# KickerBoard-new-switchreg-rerouted.net
KiCad netlist of a schematic drawn in EAGLE
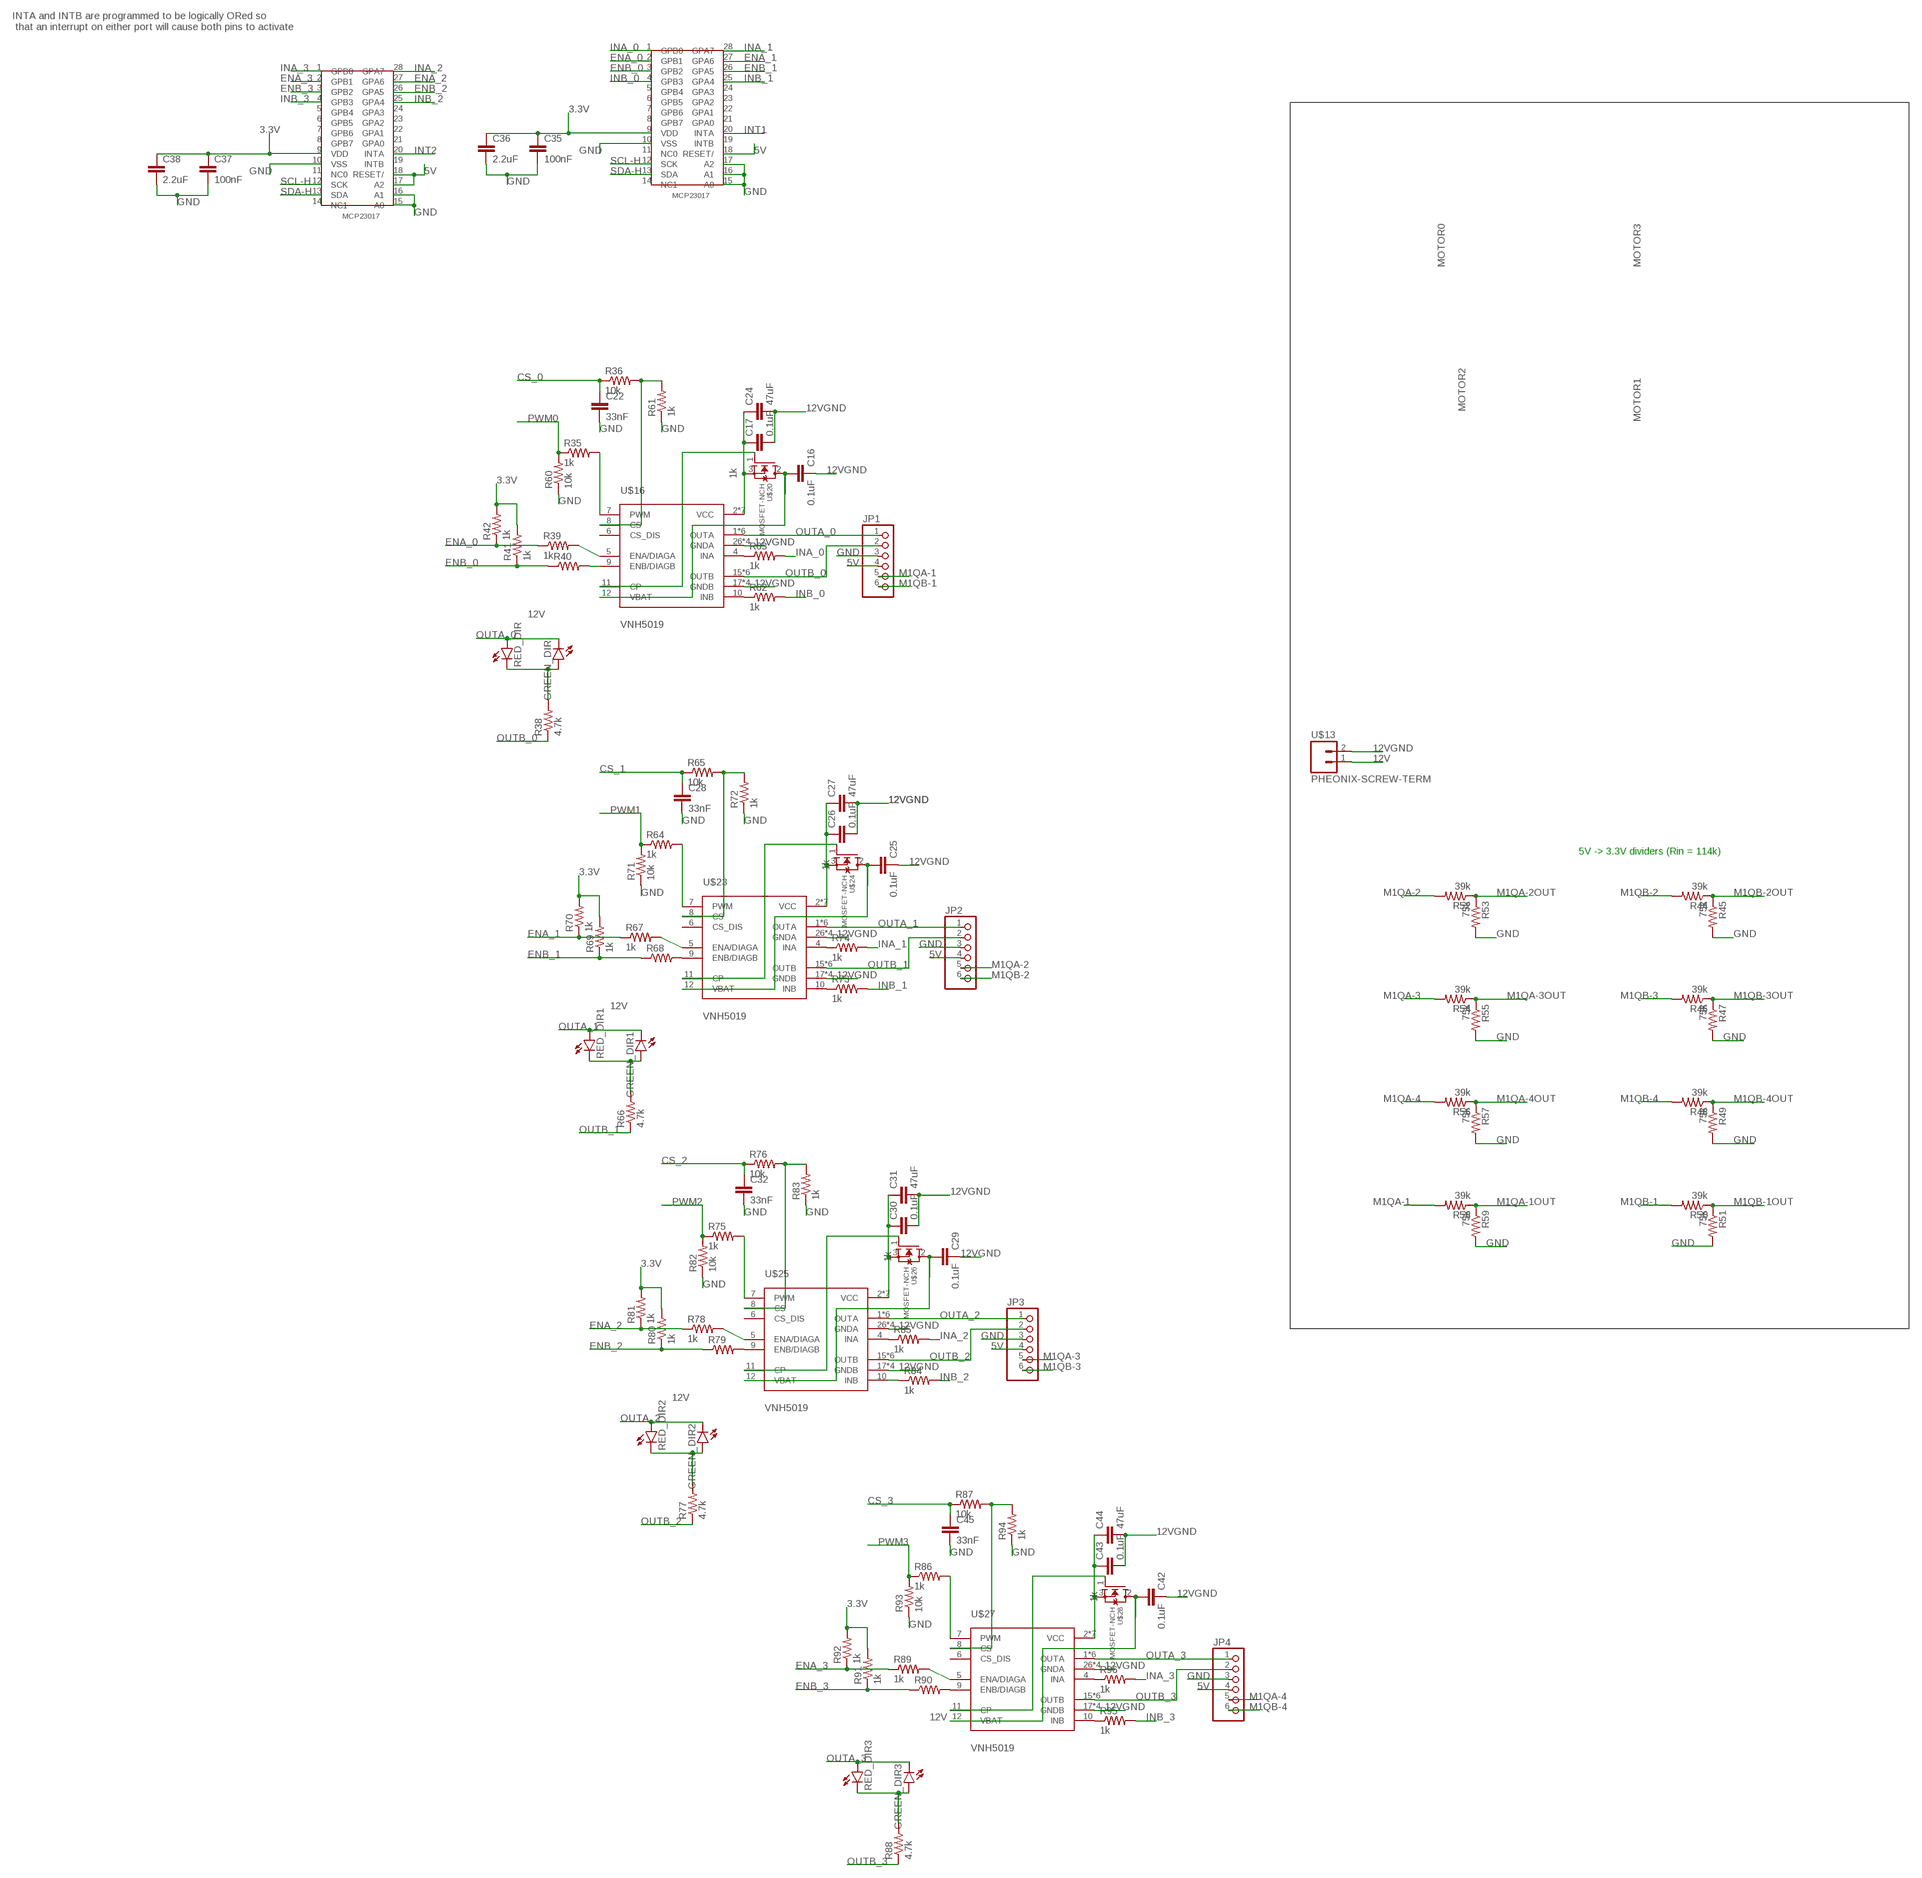
[diagram p0: schematic, sheet 1, part 1 of 3]
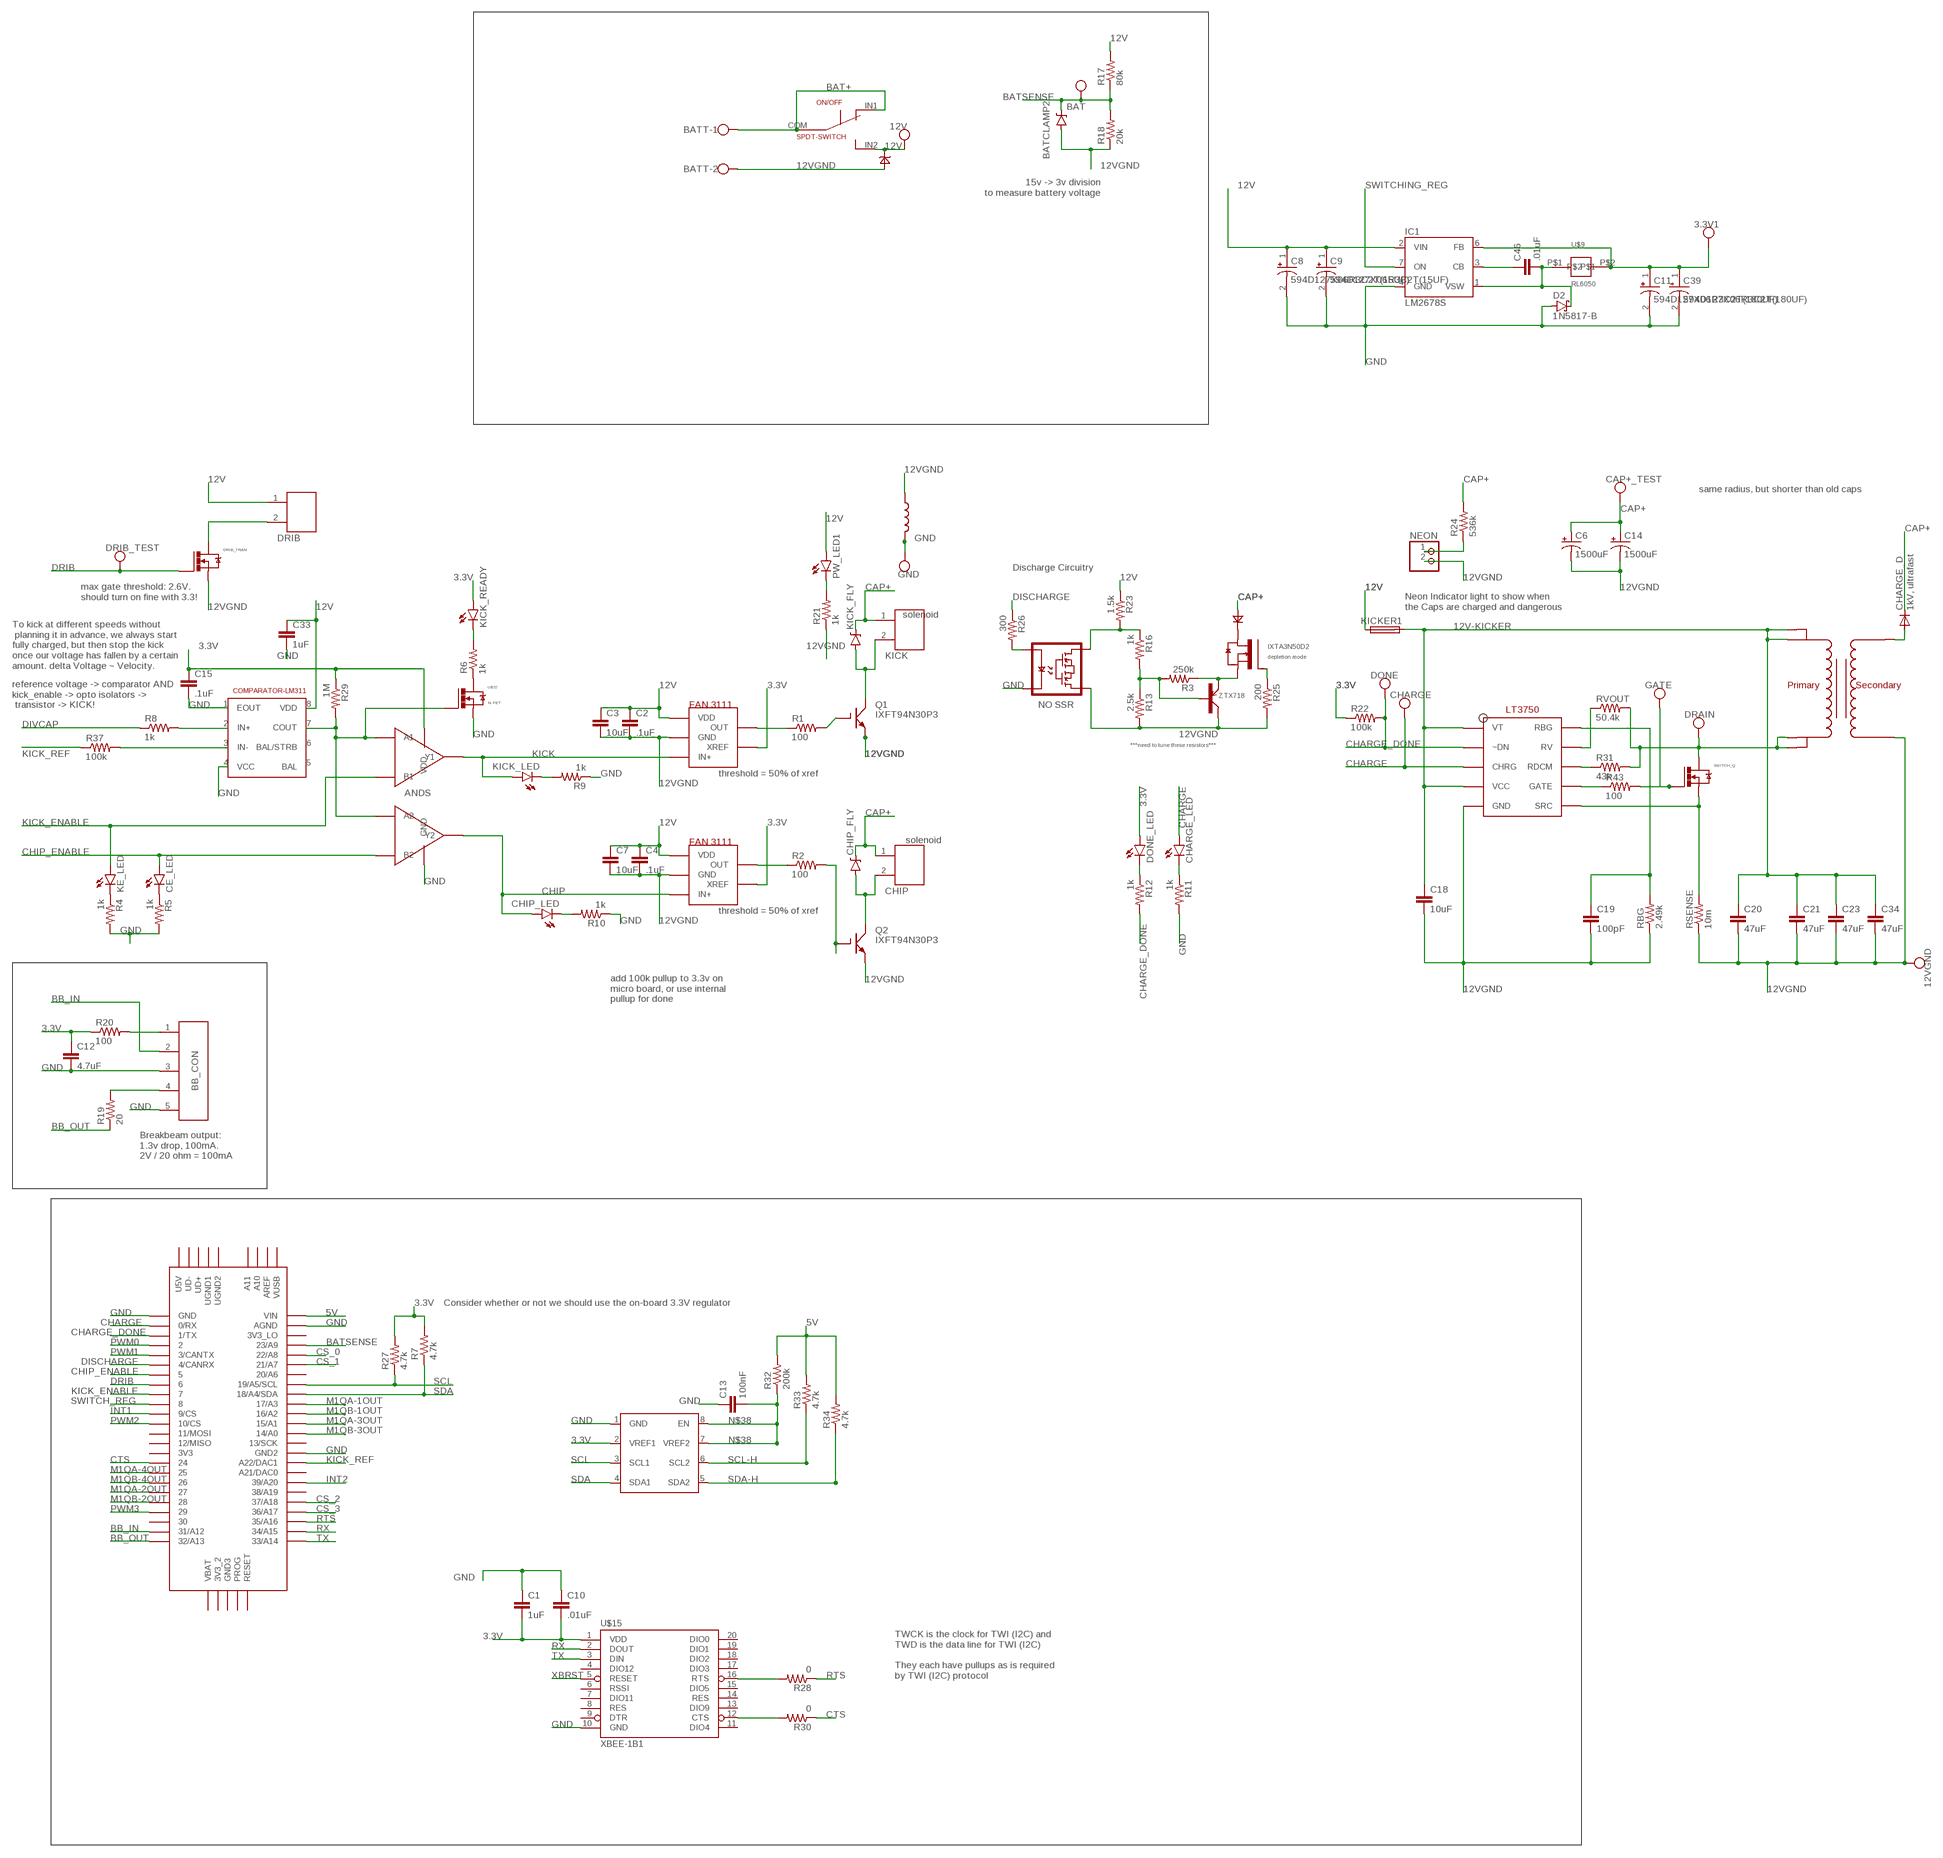
[diagram p1: schematic, sheet 1, part 2 of 3]
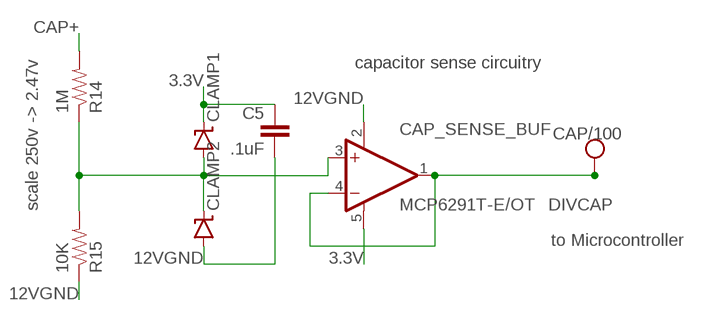
[diagram p2: schematic, sheet 1, part 3 of 3]

(export (version "E")
  (design (tool "Eeschema 10.0.6"))
  (components
    (comp (ref "3.3V1")
      (value "TEST_PT")
      (footprint "eagle-import:TESTING_PT")
      (libsource (lib "eagle-import") (part "TEST_PT"))
    )
    (comp (ref "12V")
      (value "TEST_PT")
      (footprint "eagle-import:TESTING_PT")
      (libsource (lib "eagle-import") (part "TEST_PT"))
    )
    (comp (ref "12VGND")
      (value "TEST_PT")
      (footprint "eagle-import:TESTING_PT")
      (libsource (lib "eagle-import") (part "TEST_PT"))
    )
    (comp (ref "ANDS")
      (value "AND-DUAL")
      (footprint "eagle-import:TSSOP8")
      (libsource (lib "eagle-import") (part "AND-DUAL"))
    )
    (comp (ref "BAT")
      (value "TEST_PT")
      (footprint "eagle-import:TESTING_PT")
      (libsource (lib "eagle-import") (part "TEST_PT"))
    )
    (comp (ref "BATCLAMP2")
      (value "DIODE-ZENERDO214AC")
      (footprint "eagle-import:DO214AC")
      (libsource (lib "eagle-import") (part "DIODE-ZENERDO214AC"))
    )
    (comp (ref "BATT")
      (value "W237-102")
      (footprint "eagle-import:W237-102")
      (fields (field (name "MPN") "237-102"))
      (libsource (lib "eagle-import") (part "W237-102"))
    )
    (comp (ref "BB_CON")
      (value "JST-5")
      (footprint "eagle-import:JST-5-2MM")
      (libsource (lib "eagle-import") (part "JST-5"))
    )
    (comp (ref "C1")
      (value "1uF")
      (footprint "eagle-import:1206")
      (libsource (lib "eagle-import") (part "CAP1206"))
    )
    (comp (ref "C2")
      (value ".1uF")
      (footprint "eagle-import:1206")
      (libsource (lib "eagle-import") (part "CAP1206"))
    )
    (comp (ref "C3")
      (value "10uF")
      (footprint "eagle-import:1206")
      (libsource (lib "eagle-import") (part "CAP1206"))
    )
    (comp (ref "C4")
      (value ".1uF")
      (footprint "eagle-import:1206")
      (libsource (lib "eagle-import") (part "CAP1206"))
    )
    (comp (ref "C5")
      (value ".1uF")
      (footprint "eagle-import:0805")
      (libsource (lib "eagle-import") (part "CAP0805"))
    )
    (comp (ref "C6")
      (value "1500uF")
      (footprint "eagle-import:EB35D")
      (libsource (lib "eagle-import") (part "CPOL-USE10-35"))
    )
    (comp (ref "C7")
      (value "10uF")
      (footprint "eagle-import:1206")
      (libsource (lib "eagle-import") (part "CAP1206"))
    )
    (comp (ref "C8")
      (value "594D127X06R3C2T(15UF)")
      (footprint "eagle-import:CAPCP7132X250N")
      (fields (field (name "MF") "Vishay") (field (name "MP") "594D127X06R3C2T"))
      (libsource (lib "eagle-import") (part "594D127X06R3C2T(15UF)"))
    )
    (comp (ref "C9")
      (value "594D127X06R3C2T(15UF)")
      (footprint "eagle-import:CAPCP7132X250N")
      (fields (field (name "MF") "Vishay") (field (name "MP") "594D127X06R3C2T"))
      (libsource (lib "eagle-import") (part "594D127X06R3C2T(15UF)"))
    )
    (comp (ref "C10")
      (value ".01uF")
      (footprint "eagle-import:1206")
      (libsource (lib "eagle-import") (part "CAP1206"))
    )
    (comp (ref "C11")
      (value "594D127X06R3C2T(180UF)")
      (footprint "eagle-import:CAPCP7132X250N")
      (fields (field (name "MF") "Vishay") (field (name "MP") "594D127X06R3C2T"))
      (libsource (lib "eagle-import") (part "594D127X06R3C2T(180UF)"))
    )
    (comp (ref "C12")
      (value "4.7uF")
      (footprint "eagle-import:0805")
      (libsource (lib "eagle-import") (part "CAP0805"))
    )
    (comp (ref "C13")
      (value "100nF")
      (footprint "eagle-import:0805")
      (libsource (lib "eagle-import") (part "CAP0805"))
    )
    (comp (ref "C14")
      (value "1500uF")
      (footprint "eagle-import:EB35D")
      (libsource (lib "eagle-import") (part "CPOL-USE10-35"))
    )
    (comp (ref "C15")
      (value ".1uF")
      (footprint "eagle-import:0805")
      (libsource (lib "eagle-import") (part "CAP0805"))
    )
    (comp (ref "C16")
      (value "0.1uF")
      (footprint "eagle-import:0805")
      (libsource (lib "eagle-import") (part "CAP0805"))
    )
    (comp (ref "C17")
      (value "0.1uF")
      (footprint "eagle-import:0805")
      (libsource (lib "eagle-import") (part "CAP0805"))
    )
    (comp (ref "C18")
      (value "10uF")
      (footprint "eagle-import:0805")
      (libsource (lib "eagle-import") (part "CAP0805"))
    )
    (comp (ref "C19")
      (value "100pF")
      (footprint "eagle-import:0805")
      (libsource (lib "eagle-import") (part "CAP0805"))
    )
    (comp (ref "C20")
      (value "47uF")
      (footprint "eagle-import:1206")
      (libsource (lib "eagle-import") (part "CAP1206"))
    )
    (comp (ref "C21")
      (value "47uF")
      (footprint "eagle-import:1206")
      (libsource (lib "eagle-import") (part "CAP1206"))
    )
    (comp (ref "C22")
      (value "33nF")
      (footprint "eagle-import:0805")
      (libsource (lib "eagle-import") (part "CAP0805"))
    )
    (comp (ref "C23")
      (value "47uF")
      (footprint "eagle-import:1206")
      (libsource (lib "eagle-import") (part "CAP1206"))
    )
    (comp (ref "C24")
      (value "47uF")
      (footprint "eagle-import:1206")
      (libsource (lib "eagle-import") (part "CAP1206"))
    )
    (comp (ref "C25")
      (value "0.1uF")
      (footprint "eagle-import:0805")
      (libsource (lib "eagle-import") (part "CAP0805"))
    )
    (comp (ref "C26")
      (value "0.1uF")
      (footprint "eagle-import:0805")
      (libsource (lib "eagle-import") (part "CAP0805"))
    )
    (comp (ref "C27")
      (value "47uF")
      (footprint "eagle-import:1206")
      (libsource (lib "eagle-import") (part "CAP1206"))
    )
    (comp (ref "C28")
      (value "33nF")
      (footprint "eagle-import:0805")
      (libsource (lib "eagle-import") (part "CAP0805"))
    )
    (comp (ref "C29")
      (value "0.1uF")
      (footprint "eagle-import:0805")
      (libsource (lib "eagle-import") (part "CAP0805"))
    )
    (comp (ref "C30")
      (value "0.1uF")
      (footprint "eagle-import:0805")
      (libsource (lib "eagle-import") (part "CAP0805"))
    )
    (comp (ref "C31")
      (value "47uF")
      (footprint "eagle-import:1206")
      (libsource (lib "eagle-import") (part "CAP1206"))
    )
    (comp (ref "C32")
      (value "33nF")
      (footprint "eagle-import:0805")
      (libsource (lib "eagle-import") (part "CAP0805"))
    )
    (comp (ref "C33")
      (value "1uF")
      (footprint "eagle-import:1206")
      (libsource (lib "eagle-import") (part "CAP1206"))
    )
    (comp (ref "C34")
      (value "47uF")
      (footprint "eagle-import:1206")
      (libsource (lib "eagle-import") (part "CAP1206"))
    )
    (comp (ref "C35")
      (value "100nF")
      (footprint "eagle-import:0805")
      (libsource (lib "eagle-import") (part "CAP0805"))
    )
    (comp (ref "C36")
      (value "2.2uF")
      (footprint "eagle-import:0805")
      (libsource (lib "eagle-import") (part "CAP0805"))
    )
    (comp (ref "C37")
      (value "100nF")
      (footprint "eagle-import:0805")
      (libsource (lib "eagle-import") (part "CAP0805"))
    )
    (comp (ref "C38")
      (value "2.2uF")
      (footprint "eagle-import:0805")
      (libsource (lib "eagle-import") (part "CAP0805"))
    )
    (comp (ref "C39")
      (value "594D127X06R3C2T(180UF)")
      (footprint "eagle-import:CAPCP7132X250N")
      (fields (field (name "MF") "Vishay") (field (name "MP") "594D127X06R3C2T"))
      (libsource (lib "eagle-import") (part "594D127X06R3C2T(180UF)"))
    )
    (comp (ref "C42")
      (value "0.1uF")
      (footprint "eagle-import:0805")
      (libsource (lib "eagle-import") (part "CAP0805"))
    )
    (comp (ref "C43")
      (value "0.1uF")
      (footprint "eagle-import:0805")
      (libsource (lib "eagle-import") (part "CAP0805"))
    )
    (comp (ref "C44")
      (value "47uF")
      (footprint "eagle-import:1206")
      (libsource (lib "eagle-import") (part "CAP1206"))
    )
    (comp (ref "C45")
      (value "33nF")
      (footprint "eagle-import:0805")
      (libsource (lib "eagle-import") (part "CAP0805"))
    )
    (comp (ref "C46")
      (value ".01uF")
      (footprint "eagle-import:0805")
      (libsource (lib "eagle-import") (part "CAP0805"))
    )
    (comp (ref "CAP+_TEST")
      (value "TEST_PT")
      (footprint "eagle-import:TESTING_PT")
      (libsource (lib "eagle-import") (part "TEST_PT"))
    )
    (comp (ref "CAP/100")
      (value "TEST_PT")
      (footprint "eagle-import:TESTING_PT")
      (libsource (lib "eagle-import") (part "TEST_PT"))
    )
    (comp (ref "CAP_SENSE_BUF")
      (value "MCP6291T-E/OT")
      (footprint "eagle-import:SOT23-5")
      (libsource (lib "eagle-import") (part "MCP6291T-E/OT"))
    )
    (comp (ref "CE_LED")
      (value "LED1206")
      (footprint "eagle-import:LED-1206")
      (libsource (lib "eagle-import") (part "LED1206"))
    )
    (comp (ref "CHARGE")
      (value "TEST_PT")
      (footprint "eagle-import:TESTING_PT")
      (libsource (lib "eagle-import") (part "TEST_PT"))
    )
    (comp (ref "CHARGE_D")
      (value "1kV, ultrafast")
      (footprint "eagle-import:DO214AC")
      (libsource (lib "eagle-import") (part "DIODE-DO214AC"))
    )
    (comp (ref "CHARGE_LED")
      (value "LED1206")
      (footprint "eagle-import:LED-1206")
      (libsource (lib "eagle-import") (part "LED1206"))
    )
    (comp (ref "CHARGE_U")
      (value "LT3750")
      (footprint "eagle-import:10-MSOP")
      (libsource (lib "eagle-import") (part "LT3750"))
    )
    (comp (ref "CHIP")
      (value "JST-22MM")
      (footprint "eagle-import:JST-2-2MM")
      (libsource (lib "eagle-import") (part "JST-22MM"))
    )
    (comp (ref "CHIP_FLY")
      (value "DIODE-ZENERDO214AB")
      (footprint "eagle-import:DO214AB")
      (libsource (lib "eagle-import") (part "DIODE-ZENERDO214AB"))
    )
    (comp (ref "CHIP_LED")
      (value "LED1206")
      (footprint "eagle-import:LED-1206")
      (libsource (lib "eagle-import") (part "LED1206"))
    )
    (comp (ref "CLAMP1")
      (value "DIODE-ZENERDO214AC")
      (footprint "eagle-import:DO214AC")
      (libsource (lib "eagle-import") (part "DIODE-ZENERDO214AC"))
    )
    (comp (ref "CLAMP2")
      (value "DIODE-ZENERDO214AC")
      (footprint "eagle-import:DO214AC")
      (libsource (lib "eagle-import") (part "DIODE-ZENERDO214AC"))
    )
    (comp (ref "D2")
      (value "1N5817-B")
      (footprint "eagle-import:DO41-7.6")
      (libsource (lib "eagle-import") (part "1N5817-B"))
    )
    (comp (ref "DONE")
      (value "TEST_PT")
      (footprint "eagle-import:TESTING_PT")
      (libsource (lib "eagle-import") (part "TEST_PT"))
    )
    (comp (ref "DONE_LED")
      (value "LED1206")
      (footprint "eagle-import:LED-1206")
      (libsource (lib "eagle-import") (part "LED1206"))
    )
    (comp (ref "DRAIN")
      (value "TEST_PT")
      (footprint "eagle-import:TESTING_PT")
      (libsource (lib "eagle-import") (part "TEST_PT"))
    )
    (comp (ref "DRIB")
      (value "JST-22MM")
      (footprint "eagle-import:JST-2-2MM")
      (libsource (lib "eagle-import") (part "JST-22MM"))
    )
    (comp (ref "DRIB_TEST")
      (value "TEST_PT")
      (footprint "eagle-import:TESTING_PT")
      (libsource (lib "eagle-import") (part "TEST_PT"))
    )
    (comp (ref "DRIB_TRAN")
      (value "N-MOSFETDPAK")
      (footprint "eagle-import:DPAK")
      (libsource (lib "eagle-import") (part "N-MOSFETDPAK"))
    )
    (comp (ref "GATE")
      (value "TEST_PT")
      (footprint "eagle-import:TESTING_PT")
      (libsource (lib "eagle-import") (part "TEST_PT"))
    )
    (comp (ref "GND")
      (value "TEST_PT")
      (footprint "eagle-import:TESTING_PT")
      (libsource (lib "eagle-import") (part "TEST_PT"))
    )
    (comp (ref "GREEN_DIR")
      (value "LED1206")
      (footprint "eagle-import:LED-1206")
      (libsource (lib "eagle-import") (part "LED1206"))
    )
    (comp (ref "GREEN_DIR1")
      (value "LED1206")
      (footprint "eagle-import:LED-1206")
      (libsource (lib "eagle-import") (part "LED1206"))
    )
    (comp (ref "GREEN_DIR2")
      (value "LED1206")
      (footprint "eagle-import:LED-1206")
      (libsource (lib "eagle-import") (part "LED1206"))
    )
    (comp (ref "GREEN_DIR3")
      (value "LED1206")
      (footprint "eagle-import:LED-1206")
      (libsource (lib "eagle-import") (part "LED1206"))
    )
    (comp (ref "IC1")
      (value "LM2678S")
      (footprint "eagle-import:TO263-7")
      (libsource (lib "eagle-import") (part "LM2678S"))
    )
    (comp (ref "JP1")
      (value "PINHD-1X6")
      (footprint "eagle-import:1X06")
      (libsource (lib "eagle-import") (part "PINHD-1X6"))
    )
    (comp (ref "JP2")
      (value "PINHD-1X6")
      (footprint "eagle-import:1X06")
      (libsource (lib "eagle-import") (part "PINHD-1X6"))
    )
    (comp (ref "JP3")
      (value "PINHD-1X6")
      (footprint "eagle-import:1X06")
      (libsource (lib "eagle-import") (part "PINHD-1X6"))
    )
    (comp (ref "JP4")
      (value "PINHD-1X6")
      (footprint "eagle-import:1X06")
      (libsource (lib "eagle-import") (part "PINHD-1X6"))
    )
    (comp (ref "KE_LED")
      (value "LED1206")
      (footprint "eagle-import:LED-1206")
      (libsource (lib "eagle-import") (part "LED1206"))
    )
    (comp (ref "KICK")
      (value "JST-22MM")
      (footprint "eagle-import:JST-2-2MM")
      (libsource (lib "eagle-import") (part "JST-22MM"))
    )
    (comp (ref "KICKER1")
      (value "TR5")
      (footprint "eagle-import:TR5")
      (libsource (lib "eagle-import") (part "TR5"))
    )
    (comp (ref "KICK_FLY")
      (value "DIODE-ZENERDO214AB")
      (footprint "eagle-import:DO214AB")
      (libsource (lib "eagle-import") (part "DIODE-ZENERDO214AB"))
    )
    (comp (ref "KICK_LED")
      (value "LED1206")
      (footprint "eagle-import:LED-1206")
      (libsource (lib "eagle-import") (part "LED1206"))
    )
    (comp (ref "KICK_READY")
      (value "LED1206")
      (footprint "eagle-import:LED-1206")
      (libsource (lib "eagle-import") (part "LED1206"))
    )
    (comp (ref "NEON")
      (value "PINHD-1X2")
      (footprint "eagle-import:1X02")
      (libsource (lib "eagle-import") (part "PINHD-1X2"))
    )
    (comp (ref "ON/OFF")
      (value "SPDT-SWITCH")
      (footprint "eagle-import:CK_SWITCH")
      (libsource (lib "eagle-import") (part "SPDT-SWITCH"))
    )
    (comp (ref "PW_LED1")
      (value "LED1206")
      (footprint "eagle-import:LED-1206")
      (libsource (lib "eagle-import") (part "LED1206"))
    )
    (comp (ref "Q1")
      (value "IXFT94N30P3")
      (footprint "eagle-import:TO268")
      (libsource (lib "eagle-import") (part "IXG?N170T6"))
    )
    (comp (ref "Q2")
      (value "IXFT94N30P3")
      (footprint "eagle-import:TO268")
      (libsource (lib "eagle-import") (part "IXG?N170T6"))
    )
    (comp (ref "R1")
      (value "100")
      (footprint "eagle-import:0805")
      (libsource (lib "eagle-import") (part "SparkFun-Resistors_RESISTOR0805-RES"))
    )
    (comp (ref "R2")
      (value "100")
      (footprint "eagle-import:0805")
      (libsource (lib "eagle-import") (part "SparkFun-Resistors_RESISTOR0805-RES"))
    )
    (comp (ref "R3")
      (value "250k")
      (footprint "eagle-import:0805")
      (libsource (lib "eagle-import") (part "RESISTOR0805-RES"))
    )
    (comp (ref "R4")
      (value "1k")
      (footprint "eagle-import:0805")
      (libsource (lib "eagle-import") (part "RESISTOR0805-RES"))
    )
    (comp (ref "R5")
      (value "1k")
      (footprint "eagle-import:0805")
      (libsource (lib "eagle-import") (part "RESISTOR0805-RES"))
    )
    (comp (ref "R6")
      (value "1k")
      (footprint "eagle-import:0805")
      (libsource (lib "eagle-import") (part "RESISTOR0805-RES"))
    )
    (comp (ref "R7")
      (value "4.7k")
      (footprint "eagle-import:0805")
      (libsource (lib "eagle-import") (part "SparkFun-Resistors_RESISTOR0805-RES"))
    )
    (comp (ref "R8")
      (value "1k")
      (footprint "eagle-import:0805")
      (libsource (lib "eagle-import") (part "RESISTOR0805-RES"))
    )
    (comp (ref "R9")
      (value "1k")
      (footprint "eagle-import:0805")
      (libsource (lib "eagle-import") (part "RESISTOR0805-RES"))
    )
    (comp (ref "R10")
      (value "1k")
      (footprint "eagle-import:0805")
      (libsource (lib "eagle-import") (part "RESISTOR0805-RES"))
    )
    (comp (ref "R11")
      (value "1k")
      (footprint "eagle-import:0805")
      (libsource (lib "eagle-import") (part "RESISTOR0805-RES"))
    )
    (comp (ref "R12")
      (value "1k")
      (footprint "eagle-import:0805")
      (libsource (lib "eagle-import") (part "RESISTOR0805-RES"))
    )
    (comp (ref "R13")
      (value "2.5k")
      (footprint "eagle-import:0805")
      (libsource (lib "eagle-import") (part "RESISTOR0805-RES"))
    )
    (comp (ref "R14")
      (value "1M")
      (footprint "eagle-import:0805")
      (libsource (lib "eagle-import") (part "SparkFun-Resistors_RESISTOR0805-RES"))
    )
    (comp (ref "R15")
      (value "10K")
      (footprint "eagle-import:0805")
      (libsource (lib "eagle-import") (part "SparkFun-Resistors_RESISTOR0805-RES"))
    )
    (comp (ref "R16")
      (value "1k")
      (footprint "eagle-import:0805")
      (libsource (lib "eagle-import") (part "RESISTOR0805-RES"))
    )
    (comp (ref "R17")
      (value "80k")
      (footprint "eagle-import:0805")
      (libsource (lib "eagle-import") (part "RESISTOR0805-RES"))
    )
    (comp (ref "R18")
      (value "20k")
      (footprint "eagle-import:0805")
      (libsource (lib "eagle-import") (part "RESISTOR0805-RES"))
    )
    (comp (ref "R19")
      (value "20")
      (footprint "eagle-import:0805")
      (libsource (lib "eagle-import") (part "RESISTOR0805-RES"))
    )
    (comp (ref "R20")
      (value "100")
      (footprint "eagle-import:0805")
      (libsource (lib "eagle-import") (part "RESISTOR0805-RES"))
    )
    (comp (ref "R21")
      (value "1k")
      (footprint "eagle-import:0805")
      (libsource (lib "eagle-import") (part "RESISTOR0805-RES"))
    )
    (comp (ref "R22")
      (value "100k")
      (footprint "eagle-import:0805")
      (libsource (lib "eagle-import") (part "RESISTOR0805-RES"))
    )
    (comp (ref "R23")
      (value "1.5k")
      (footprint "eagle-import:0805")
      (libsource (lib "eagle-import") (part "RESISTOR0805-RES"))
    )
    (comp (ref "R24")
      (value "536k")
      (footprint "eagle-import:0805")
      (libsource (lib "eagle-import") (part "RESISTOR0805-RES"))
    )
    (comp (ref "R25")
      (value "200")
      (footprint "eagle-import:0805")
      (libsource (lib "eagle-import") (part "RESISTOR0805-RES"))
    )
    (comp (ref "R26")
      (value "300")
      (footprint "eagle-import:0805")
      (libsource (lib "eagle-import") (part "RESISTOR0805-RES"))
    )
    (comp (ref "R27")
      (value "4.7k")
      (footprint "eagle-import:0805")
      (libsource (lib "eagle-import") (part "SparkFun-Resistors_RESISTOR0805-RES"))
    )
    (comp (ref "R28")
      (value "0")
      (footprint "eagle-import:0805")
      (libsource (lib "eagle-import") (part "SparkFun-Resistors_RESISTOR0805-RES"))
    )
    (comp (ref "R29")
      (value "1M")
      (footprint "eagle-import:0805")
      (libsource (lib "eagle-import") (part "RESISTOR0805-RES"))
    )
    (comp (ref "R30")
      (value "0")
      (footprint "eagle-import:0805")
      (libsource (lib "eagle-import") (part "SparkFun-Resistors_RESISTOR0805-RES"))
    )
    (comp (ref "R31")
      (value "43k")
      (footprint "eagle-import:0805")
      (libsource (lib "eagle-import") (part "RESISTOR0805-RES"))
    )
    (comp (ref "R32")
      (value "200k")
      (footprint "eagle-import:0805")
      (libsource (lib "eagle-import") (part "SparkFun-Resistors_RESISTOR0805-RES"))
    )
    (comp (ref "R33")
      (value "4.7k")
      (footprint "eagle-import:0805")
      (libsource (lib "eagle-import") (part "SparkFun-Resistors_RESISTOR0805-RES"))
    )
    (comp (ref "R34")
      (value "4.7k")
      (footprint "eagle-import:0805")
      (libsource (lib "eagle-import") (part "SparkFun-Resistors_RESISTOR0805-RES"))
    )
    (comp (ref "R35")
      (value "1k")
      (footprint "eagle-import:0805")
      (libsource (lib "eagle-import") (part "RESISTOR0805-RES"))
    )
    (comp (ref "R36")
      (value "10k")
      (footprint "eagle-import:0805")
      (libsource (lib "eagle-import") (part "RESISTOR0805-RES"))
    )
    (comp (ref "R37")
      (value "100k")
      (footprint "eagle-import:0805")
      (libsource (lib "eagle-import") (part "RESISTOR0805-RES"))
    )
    (comp (ref "R38")
      (value "4.7k")
      (footprint "eagle-import:0805")
      (libsource (lib "eagle-import") (part "RESISTOR0805-RES"))
    )
    (comp (ref "R39")
      (value "1k")
      (footprint "eagle-import:0805")
      (libsource (lib "eagle-import") (part "RESISTOR0805-RES"))
    )
    (comp (ref "R40")
      (value "1k")
      (footprint "eagle-import:0805")
      (libsource (lib "eagle-import") (part "RESISTOR0805-RES"))
    )
    (comp (ref "R41")
      (value "1k")
      (footprint "eagle-import:0805")
      (libsource (lib "eagle-import") (part "RESISTOR0805-RES"))
    )
    (comp (ref "R42")
      (value "1k")
      (footprint "eagle-import:0805")
      (libsource (lib "eagle-import") (part "RESISTOR0805-RES"))
    )
    (comp (ref "R43")
      (value "100")
      (footprint "eagle-import:0805")
      (libsource (lib "eagle-import") (part "RESISTOR0805-RES"))
    )
    (comp (ref "R44")
      (value "39k")
      (footprint "eagle-import:0805")
      (libsource (lib "eagle-import") (part "RESISTOR0805-RES"))
    )
    (comp (ref "R45")
      (value "75k")
      (footprint "eagle-import:0805")
      (libsource (lib "eagle-import") (part "RESISTOR0805-RES"))
    )
    (comp (ref "R46")
      (value "39k")
      (footprint "eagle-import:0805")
      (libsource (lib "eagle-import") (part "RESISTOR0805-RES"))
    )
    (comp (ref "R47")
      (value "75k")
      (footprint "eagle-import:0805")
      (libsource (lib "eagle-import") (part "RESISTOR0805-RES"))
    )
    (comp (ref "R48")
      (value "39k")
      (footprint "eagle-import:0805")
      (libsource (lib "eagle-import") (part "RESISTOR0805-RES"))
    )
    (comp (ref "R49")
      (value "75k")
      (footprint "eagle-import:0805")
      (libsource (lib "eagle-import") (part "RESISTOR0805-RES"))
    )
    (comp (ref "R50")
      (value "39k")
      (footprint "eagle-import:0805")
      (libsource (lib "eagle-import") (part "RESISTOR0805-RES"))
    )
    (comp (ref "R51")
      (value "75k")
      (footprint "eagle-import:0805")
      (libsource (lib "eagle-import") (part "RESISTOR0805-RES"))
    )
    (comp (ref "R52")
      (value "39k")
      (footprint "eagle-import:0805")
      (libsource (lib "eagle-import") (part "RESISTOR0805-RES"))
    )
    (comp (ref "R53")
      (value "75k")
      (footprint "eagle-import:0805")
      (libsource (lib "eagle-import") (part "RESISTOR0805-RES"))
    )
    (comp (ref "R54")
      (value "39k")
      (footprint "eagle-import:0805")
      (libsource (lib "eagle-import") (part "RESISTOR0805-RES"))
    )
    (comp (ref "R55")
      (value "75k")
      (footprint "eagle-import:0805")
      (libsource (lib "eagle-import") (part "RESISTOR0805-RES"))
    )
    (comp (ref "R56")
      (value "39k")
      (footprint "eagle-import:0805")
      (libsource (lib "eagle-import") (part "RESISTOR0805-RES"))
    )
    (comp (ref "R57")
      (value "75k")
      (footprint "eagle-import:0805")
      (libsource (lib "eagle-import") (part "RESISTOR0805-RES"))
    )
    (comp (ref "R58")
      (value "39k")
      (footprint "eagle-import:0805")
      (libsource (lib "eagle-import") (part "RESISTOR0805-RES"))
    )
    (comp (ref "R59")
      (value "75k")
      (footprint "eagle-import:0805")
      (libsource (lib "eagle-import") (part "RESISTOR0805-RES"))
    )
    (comp (ref "R60")
      (value "10k")
      (footprint "eagle-import:0805")
      (libsource (lib "eagle-import") (part "RESISTOR0805-RES"))
    )
    (comp (ref "R61")
      (value "1k")
      (footprint "eagle-import:0805")
      (libsource (lib "eagle-import") (part "RESISTOR0805-RES"))
    )
    (comp (ref "R62")
      (value "1k")
      (footprint "eagle-import:0805")
      (libsource (lib "eagle-import") (part "RESISTOR0805-RES"))
    )
    (comp (ref "R63")
      (value "1k")
      (footprint "eagle-import:0805")
      (libsource (lib "eagle-import") (part "RESISTOR0805-RES"))
    )
    (comp (ref "R64")
      (value "1k")
      (footprint "eagle-import:0805")
      (libsource (lib "eagle-import") (part "RESISTOR0805-RES"))
    )
    (comp (ref "R65")
      (value "10k")
      (footprint "eagle-import:0805")
      (libsource (lib "eagle-import") (part "RESISTOR0805-RES"))
    )
    (comp (ref "R66")
      (value "4.7k")
      (footprint "eagle-import:0805")
      (libsource (lib "eagle-import") (part "RESISTOR0805-RES"))
    )
    (comp (ref "R67")
      (value "1k")
      (footprint "eagle-import:0805")
      (libsource (lib "eagle-import") (part "RESISTOR0805-RES"))
    )
    (comp (ref "R68")
      (value "1k")
      (footprint "eagle-import:0805")
      (libsource (lib "eagle-import") (part "RESISTOR0805-RES"))
    )
    (comp (ref "R69")
      (value "1k")
      (footprint "eagle-import:0805")
      (libsource (lib "eagle-import") (part "RESISTOR0805-RES"))
    )
    (comp (ref "R70")
      (value "1k")
      (footprint "eagle-import:0805")
      (libsource (lib "eagle-import") (part "RESISTOR0805-RES"))
    )
    (comp (ref "R71")
      (value "10k")
      (footprint "eagle-import:0805")
      (libsource (lib "eagle-import") (part "RESISTOR0805-RES"))
    )
    (comp (ref "R72")
      (value "1k")
      (footprint "eagle-import:0805")
      (libsource (lib "eagle-import") (part "RESISTOR0805-RES"))
    )
    (comp (ref "R73")
      (value "1k")
      (footprint "eagle-import:0805")
      (libsource (lib "eagle-import") (part "RESISTOR0805-RES"))
    )
    (comp (ref "R74")
      (value "1k")
      (footprint "eagle-import:0805")
      (libsource (lib "eagle-import") (part "RESISTOR0805-RES"))
    )
    (comp (ref "R75")
      (value "1k")
      (footprint "eagle-import:0805")
      (libsource (lib "eagle-import") (part "RESISTOR0805-RES"))
    )
    (comp (ref "R76")
      (value "10k")
      (footprint "eagle-import:0805")
      (libsource (lib "eagle-import") (part "RESISTOR0805-RES"))
    )
    (comp (ref "R77")
      (value "4.7k")
      (footprint "eagle-import:0805")
      (libsource (lib "eagle-import") (part "RESISTOR0805-RES"))
    )
    (comp (ref "R78")
      (value "1k")
      (footprint "eagle-import:0805")
      (libsource (lib "eagle-import") (part "RESISTOR0805-RES"))
    )
    (comp (ref "R79")
      (value "1k")
      (footprint "eagle-import:0805")
      (libsource (lib "eagle-import") (part "RESISTOR0805-RES"))
    )
    (comp (ref "R80")
      (value "1k")
      (footprint "eagle-import:0805")
      (libsource (lib "eagle-import") (part "RESISTOR0805-RES"))
    )
    (comp (ref "R81")
      (value "1k")
      (footprint "eagle-import:0805")
      (libsource (lib "eagle-import") (part "RESISTOR0805-RES"))
    )
    (comp (ref "R82")
      (value "10k")
      (footprint "eagle-import:0805")
      (libsource (lib "eagle-import") (part "RESISTOR0805-RES"))
    )
    (comp (ref "R83")
      (value "1k")
      (footprint "eagle-import:0805")
      (libsource (lib "eagle-import") (part "RESISTOR0805-RES"))
    )
    (comp (ref "R84")
      (value "1k")
      (footprint "eagle-import:0805")
      (libsource (lib "eagle-import") (part "RESISTOR0805-RES"))
    )
    (comp (ref "R85")
      (value "1k")
      (footprint "eagle-import:0805")
      (libsource (lib "eagle-import") (part "RESISTOR0805-RES"))
    )
    (comp (ref "R86")
      (value "1k")
      (footprint "eagle-import:0805")
      (libsource (lib "eagle-import") (part "RESISTOR0805-RES"))
    )
    (comp (ref "R87")
      (value "10k")
      (footprint "eagle-import:0805")
      (libsource (lib "eagle-import") (part "RESISTOR0805-RES"))
    )
    (comp (ref "R88")
      (value "4.7k")
      (footprint "eagle-import:0805")
      (libsource (lib "eagle-import") (part "RESISTOR0805-RES"))
    )
    (comp (ref "R89")
      (value "1k")
      (footprint "eagle-import:0805")
      (libsource (lib "eagle-import") (part "RESISTOR0805-RES"))
    )
    (comp (ref "R90")
      (value "1k")
      (footprint "eagle-import:0805")
      (libsource (lib "eagle-import") (part "RESISTOR0805-RES"))
    )
    (comp (ref "R91")
      (value "1k")
      (footprint "eagle-import:0805")
      (libsource (lib "eagle-import") (part "RESISTOR0805-RES"))
    )
    (comp (ref "R92")
      (value "1k")
      (footprint "eagle-import:0805")
      (libsource (lib "eagle-import") (part "RESISTOR0805-RES"))
    )
    (comp (ref "R93")
      (value "10k")
      (footprint "eagle-import:0805")
      (libsource (lib "eagle-import") (part "RESISTOR0805-RES"))
    )
    (comp (ref "R94")
      (value "1k")
      (footprint "eagle-import:0805")
      (libsource (lib "eagle-import") (part "RESISTOR0805-RES"))
    )
    (comp (ref "R95")
      (value "1k")
      (footprint "eagle-import:0805")
      (libsource (lib "eagle-import") (part "RESISTOR0805-RES"))
    )
    (comp (ref "R96")
      (value "1k")
      (footprint "eagle-import:0805")
      (libsource (lib "eagle-import") (part "RESISTOR0805-RES"))
    )
    (comp (ref "RBG")
      (value "2.49k")
      (footprint "eagle-import:0805")
      (libsource (lib "eagle-import") (part "RESISTOR0805-RES"))
    )
    (comp (ref "RED_DIR")
      (value "LED1206")
      (footprint "eagle-import:LED-1206")
      (libsource (lib "eagle-import") (part "LED1206"))
    )
    (comp (ref "RED_DIR1")
      (value "LED1206")
      (footprint "eagle-import:LED-1206")
      (libsource (lib "eagle-import") (part "LED1206"))
    )
    (comp (ref "RED_DIR2")
      (value "LED1206")
      (footprint "eagle-import:LED-1206")
      (libsource (lib "eagle-import") (part "LED1206"))
    )
    (comp (ref "RED_DIR3")
      (value "LED1206")
      (footprint "eagle-import:LED-1206")
      (libsource (lib "eagle-import") (part "LED1206"))
    )
    (comp (ref "RSENSE")
      (value "10m")
      (footprint "eagle-import:R2512")
      (libsource (lib "eagle-import") (part "RESISTOR2512"))
    )
    (comp (ref "RVOUT")
      (value "50.4k")
      (footprint "eagle-import:0805")
      (libsource (lib "eagle-import") (part "RESISTOR0805-RES"))
    )
    (comp (ref "SWITCH_Q")
      (value "N-MOSFETDPAK")
      (footprint "eagle-import:DPAK")
      (libsource (lib "eagle-import") (part "N-MOSFETDPAK"))
    )
    (comp (ref "U$1")
      (value "FAN31111")
      (footprint "eagle-import:SOT23-5")
      (libsource (lib "eagle-import") (part "FAN31111"))
    )
    (comp (ref "U$2")
      (value "IXTA3N50D2")
      (footprint "eagle-import:TO-263")
      (libsource (lib "eagle-import") (part "IXTA3N50D2"))
    )
    (comp (ref "U$3")
      (value "32052-TRANSFORMER")
      (footprint "eagle-import:10-TRANSFORMER")
      (libsource (lib "eagle-import") (part "32052-TRANSFORMER"))
    )
    (comp (ref "U$4")
      (value "FAN31111")
      (footprint "eagle-import:SOT23-5")
      (libsource (lib "eagle-import") (part "FAN31111"))
    )
    (comp (ref "U$5")
      (value "VO1400AEFTR")
      (footprint "eagle-import:SOP4")
      (libsource (lib "eagle-import") (part "VO1400AEFTR"))
    )
    (comp (ref "U$6")
      (value "ZTX718")
      (footprint "eagle-import:TO92")
      (libsource (lib "eagle-import") (part "ZTX718"))
    )
    (comp (ref "U$7")
      (value "1N4007")
      (footprint "eagle-import:THROUGH-HOLE-2")
      (libsource (lib "eagle-import") (part "1N4007"))
    )
    (comp (ref "U$8")
      (value "PCA9306")
      (footprint "eagle-import:SOIC8")
      (libsource (lib "eagle-import") (part "PCA9306"))
    )
    (comp (ref "U$9")
      (value "RL6050")
      (footprint "eagle-import:RL6050")
      (libsource (lib "eagle-import") (part "RL6050"))
    )
    (comp (ref "U$12")
      (value "13VZENER")
      (footprint "eagle-import:THROUGH-HOLE-2")
      (libsource (lib "eagle-import") (part "13VZENER"))
    )
    (comp (ref "U$13")
      (value "PHEONIX-SCREW-TERM")
      (footprint "eagle-import:1X02-PHEONIX")
      (libsource (lib "eagle-import") (part "PHEONIX-SCREW-TERM"))
    )
    (comp (ref "U$14")
      (value "TEENSY_3.5/3.6")
      (footprint "eagle-import:TEENSY_3.5_3.6")
      (libsource (lib "eagle-import") (part "TEENSY_3.5/3.6"))
    )
    (comp (ref "U$15")
      (value "XBEE-1B1")
      (footprint "eagle-import:XBEE-1")
      (libsource (lib "eagle-import") (part "XBEE-1B1"))
    )
    (comp (ref "U$16")
      (value "VNH5019")
      (footprint "eagle-import:MULTIPOWERSO-30")
      (libsource (lib "eagle-import") (part "VNH5019"))
    )
    (comp (ref "U$17")
      (value "IO-EXPANDER")
      (footprint "eagle-import:SSOP")
      (libsource (lib "eagle-import") (part "IO-EXPANDER"))
    )
    (comp (ref "U$18")
      (value "LM311")
      (footprint "eagle-import:SOIC8")
      (libsource (lib "eagle-import") (part "LM311"))
    )
    (comp (ref "U$19")
      (value "INDUCTOR")
      (footprint "eagle-import:0805")
      (libsource (lib "eagle-import") (part "INDUCTOR"))
    )
    (comp (ref "U$20")
      (value "MOSFET-NCH")
      (footprint "eagle-import:TO252-3")
      (libsource (lib "eagle-import") (part "MOSFET-NCH"))
    )
    (comp (ref "U$21")
      (value "IO-EXPANDER")
      (footprint "eagle-import:SSOP")
      (libsource (lib "eagle-import") (part "IO-EXPANDER"))
    )
    (comp (ref "U$22")
      (value "N-FET")
      (footprint "eagle-import:SOT-23")
      (libsource (lib "eagle-import") (part "N-FET"))
    )
    (comp (ref "U$23")
      (value "VNH5019")
      (footprint "eagle-import:MULTIPOWERSO-30")
      (libsource (lib "eagle-import") (part "VNH5019"))
    )
    (comp (ref "U$24")
      (value "MOSFET-NCH")
      (footprint "eagle-import:TO252-3")
      (libsource (lib "eagle-import") (part "MOSFET-NCH"))
    )
    (comp (ref "U$25")
      (value "VNH5019")
      (footprint "eagle-import:MULTIPOWERSO-30")
      (libsource (lib "eagle-import") (part "VNH5019"))
    )
    (comp (ref "U$26")
      (value "MOSFET-NCH")
      (footprint "eagle-import:TO252-3")
      (libsource (lib "eagle-import") (part "MOSFET-NCH"))
    )
    (comp (ref "U$27")
      (value "VNH5019")
      (footprint "eagle-import:MULTIPOWERSO-30")
      (libsource (lib "eagle-import") (part "VNH5019"))
    )
    (comp (ref "U$28")
      (value "MOSFET-NCH")
      (footprint "eagle-import:TO252-3")
      (libsource (lib "eagle-import") (part "MOSFET-NCH"))
    )
  )
  (nets
    (net (code "1") (name "/3.3V") (class "Default")
      (node (ref "ANDS") (pin "P$8") (pinfunction "VDD_P$8") (pintype "bidirectional"))
      (node (ref "C1") (pin "2") (pinfunction "2_2") (pintype "passive"))
      (node (ref "C10") (pin "2") (pinfunction "2_2") (pintype "passive"))
      (node (ref "C12") (pin "1") (pinfunction "1_1") (pintype "passive"))
      (node (ref "C15") (pin "1") (pinfunction "1_1") (pintype "passive"))
      (node (ref "C35") (pin "1") (pinfunction "1_1") (pintype "passive"))
      (node (ref "C36") (pin "1") (pinfunction "1_1") (pintype "passive"))
      (node (ref "C37") (pin "1") (pinfunction "1_1") (pintype "passive"))
      (node (ref "C38") (pin "1") (pinfunction "1_1") (pintype "passive"))
      (node (ref "C5") (pin "1") (pinfunction "1_1") (pintype "passive"))
      (node (ref "CAP_SENSE_BUF") (pin "5") (pinfunction "V+_5") (pintype "power_in"))
      (node (ref "CLAMP1") (pin "C") (pinfunction "C_C") (pintype "passive"))
      (node (ref "DONE_LED") (pin "A") (pinfunction "A_A") (pintype "passive"))
      (node (ref "KICK_READY") (pin "A") (pinfunction "A_A") (pintype "passive"))
      (node (ref "R20") (pin "1") (pinfunction "1_1") (pintype "passive"))
      (node (ref "R22") (pin "1") (pinfunction "1_1") (pintype "passive"))
      (node (ref "R27") (pin "2") (pinfunction "2_2") (pintype "passive"))
      (node (ref "R29") (pin "1") (pinfunction "1_1") (pintype "passive"))
      (node (ref "R41") (pin "2") (pinfunction "2_2") (pintype "passive"))
      (node (ref "R42") (pin "2") (pinfunction "2_2") (pintype "passive"))
      (node (ref "R69") (pin "2") (pinfunction "2_2") (pintype "passive"))
      (node (ref "R7") (pin "2") (pinfunction "2_2") (pintype "passive"))
      (node (ref "R70") (pin "2") (pinfunction "2_2") (pintype "passive"))
      (node (ref "R80") (pin "2") (pinfunction "2_2") (pintype "passive"))
      (node (ref "R81") (pin "2") (pinfunction "2_2") (pintype "passive"))
      (node (ref "R91") (pin "2") (pinfunction "2_2") (pintype "passive"))
      (node (ref "R92") (pin "2") (pinfunction "2_2") (pintype "passive"))
      (node (ref "U$1") (pin "4") (pinfunction "XREF_4") (pintype "input"))
      (node (ref "U$15") (pin "1") (pinfunction "VDD_1") (pintype "power_in"))
      (node (ref "U$17") (pin "9") (pinfunction "VDD_9") (pintype "bidirectional"))
      (node (ref "U$21") (pin "9") (pinfunction "VDD_9") (pintype "bidirectional"))
      (node (ref "U$4") (pin "4") (pinfunction "XREF_4") (pintype "input"))
      (node (ref "U$8") (pin "2") (pinfunction "VREF1_2") (pintype "bidirectional"))
    )
    (net (code "2") (name "/5V") (class "Default")
      (node (ref "JP1") (pin "4") (pinfunction "4_4") (pintype "passive"))
      (node (ref "JP2") (pin "4") (pinfunction "4_4") (pintype "passive"))
      (node (ref "JP3") (pin "4") (pinfunction "4_4") (pintype "passive"))
      (node (ref "JP4") (pin "4") (pinfunction "4_4") (pintype "passive"))
      (node (ref "R32") (pin "2") (pinfunction "2_2") (pintype "passive"))
      (node (ref "R33") (pin "2") (pinfunction "2_2") (pintype "passive"))
      (node (ref "R34") (pin "2") (pinfunction "2_2") (pintype "passive"))
      (node (ref "U$14") (pin "VIN") (pinfunction "VIN_VIN") (pintype "bidirectional"))
      (node (ref "U$17") (pin "18") (pinfunction "RESET/_18") (pintype "bidirectional"))
      (node (ref "U$21") (pin "17") (pinfunction "A2_17") (pintype "bidirectional"))
      (node (ref "U$21") (pin "18") (pinfunction "RESET/_18") (pintype "bidirectional"))
    )
    (net (code "3") (name "/12V") (class "Default")
      (node (ref "12V") (pin "P$1") (pinfunction "P$1_P$1") (pintype "bidirectional"))
      (node (ref "C16") (pin "1") (pinfunction "1_1") (pintype "passive"))
      (node (ref "C2") (pin "1") (pinfunction "1_1") (pintype "passive"))
      (node (ref "C25") (pin "1") (pinfunction "1_1") (pintype "passive"))
      (node (ref "C29") (pin "1") (pinfunction "1_1") (pintype "passive"))
      (node (ref "C3") (pin "1") (pinfunction "1_1") (pintype "passive"))
      (node (ref "C33") (pin "1") (pinfunction "1_1") (pintype "passive"))
      (node (ref "C4") (pin "1") (pinfunction "1_1") (pintype "passive"))
      (node (ref "C42") (pin "1") (pinfunction "1_1") (pintype "passive"))
      (node (ref "C7") (pin "1") (pinfunction "1_1") (pintype "passive"))
      (node (ref "C8") (pin "1") (pinfunction "1_1") (pintype "passive"))
      (node (ref "C9") (pin "1") (pinfunction "1_1") (pintype "passive"))
      (node (ref "DRIB") (pin "1") (pinfunction "P$1_1") (pintype "bidirectional"))
      (node (ref "IC1") (pin "2") (pinfunction "VIN_2") (pintype "power_in"))
      (node (ref "KICKER1") (pin "1") (pinfunction "1_1") (pintype "passive"))
      (node (ref "ON/OFF") (pin "IN2") (pinfunction "P2_IN2") (pintype "bidirectional"))
      (node (ref "PW_LED1") (pin "A") (pinfunction "A_A") (pintype "passive"))
      (node (ref "R17") (pin "2") (pinfunction "2_2") (pintype "passive"))
      (node (ref "R23") (pin "1") (pinfunction "1_1") (pintype "passive"))
      (node (ref "U$1") (pin "1") (pinfunction "VDD_1") (pintype "power_in"))
      (node (ref "U$12") (pin "-") (pinfunction "-_-") (pintype "bidirectional"))
      (node (ref "U$13") (pin "1") (pinfunction "1_1") (pintype "passive"))
      (node (ref "U$16") (pin "12") (pinfunction "VBAT_12") (pintype "bidirectional"))
      (node (ref "U$18") (pin "8") (pinfunction "VDD_8") (pintype "bidirectional"))
      (node (ref "U$20") (pin "2") (pinfunction "D_2") (pintype "bidirectional"))
      (node (ref "U$23") (pin "12") (pinfunction "VBAT_12") (pintype "bidirectional"))
      (node (ref "U$24") (pin "2") (pinfunction "D_2") (pintype "bidirectional"))
      (node (ref "U$25") (pin "12") (pinfunction "VBAT_12") (pintype "bidirectional"))
      (node (ref "U$26") (pin "2") (pinfunction "D_2") (pintype "bidirectional"))
      (node (ref "U$27") (pin "12") (pinfunction "VBAT_12") (pintype "bidirectional"))
      (node (ref "U$28") (pin "2") (pinfunction "D_2") (pintype "bidirectional"))
      (node (ref "U$4") (pin "1") (pinfunction "VDD_1") (pintype "power_in"))
    )
    (net (code "4") (name "/12V-KICKER") (class "Default")
      (node (ref "C18") (pin "1") (pinfunction "1_1") (pintype "passive"))
      (node (ref "C20") (pin "1") (pinfunction "1_1") (pintype "passive"))
      (node (ref "C21") (pin "1") (pinfunction "1_1") (pintype "passive"))
      (node (ref "C23") (pin "1") (pinfunction "1_1") (pintype "passive"))
      (node (ref "C34") (pin "1") (pinfunction "1_1") (pintype "passive"))
      (node (ref "CHARGE_U") (pin "P$1") (pinfunction "VT_P$1") (pintype "bidirectional"))
      (node (ref "CHARGE_U") (pin "P$4") (pinfunction "VCC_P$4") (pintype "bidirectional"))
      (node (ref "KICKER1") (pin "2") (pinfunction "2_2") (pintype "passive"))
      (node (ref "U$3") (pin "P$4") (pinfunction "P$4_P$4") (pintype "bidirectional"))
      (node (ref "U$3") (pin "P$5") (pinfunction "P$5_P$5") (pintype "bidirectional"))
    )
    (net (code "5") (name "/12VGND") (class "Default")
      (node (ref "12VGND") (pin "P$1") (pinfunction "P$1_P$1") (pintype "bidirectional"))
      (node (ref "BATCLAMP2") (pin "A") (pinfunction "A_A") (pintype "passive"))
      (node (ref "BATT") (pin "2") (pinfunction "KL_2") (pintype "passive"))
      (node (ref "C14") (pin "-") (pinfunction "-_-") (pintype "passive"))
      (node (ref "C16") (pin "2") (pinfunction "2_2") (pintype "passive"))
      (node (ref "C17") (pin "2") (pinfunction "2_2") (pintype "passive"))
      (node (ref "C18") (pin "2") (pinfunction "2_2") (pintype "passive"))
      (node (ref "C19") (pin "2") (pinfunction "2_2") (pintype "passive"))
      (node (ref "C2") (pin "2") (pinfunction "2_2") (pintype "passive"))
      (node (ref "C20") (pin "2") (pinfunction "2_2") (pintype "passive"))
      (node (ref "C21") (pin "2") (pinfunction "2_2") (pintype "passive"))
      (node (ref "C23") (pin "2") (pinfunction "2_2") (pintype "passive"))
      (node (ref "C24") (pin "2") (pinfunction "2_2") (pintype "passive"))
      (node (ref "C25") (pin "2") (pinfunction "2_2") (pintype "passive"))
      (node (ref "C26") (pin "2") (pinfunction "2_2") (pintype "passive"))
      (node (ref "C27") (pin "2") (pinfunction "2_2") (pintype "passive"))
      (node (ref "C29") (pin "2") (pinfunction "2_2") (pintype "passive"))
      (node (ref "C3") (pin "2") (pinfunction "2_2") (pintype "passive"))
      (node (ref "C30") (pin "2") (pinfunction "2_2") (pintype "passive"))
      (node (ref "C31") (pin "2") (pinfunction "2_2") (pintype "passive"))
      (node (ref "C34") (pin "2") (pinfunction "2_2") (pintype "passive"))
      (node (ref "C4") (pin "2") (pinfunction "2_2") (pintype "passive"))
      (node (ref "C42") (pin "2") (pinfunction "2_2") (pintype "passive"))
      (node (ref "C43") (pin "2") (pinfunction "2_2") (pintype "passive"))
      (node (ref "C44") (pin "2") (pinfunction "2_2") (pintype "passive"))
      (node (ref "C5") (pin "2") (pinfunction "2_2") (pintype "passive"))
      (node (ref "C6") (pin "-") (pinfunction "-_-") (pintype "passive"))
      (node (ref "C7") (pin "2") (pinfunction "2_2") (pintype "passive"))
      (node (ref "CAP_SENSE_BUF") (pin "2") (pinfunction "V-_2") (pintype "power_in"))
      (node (ref "CHARGE_U") (pin "P$5") (pinfunction "GND_P$5") (pintype "bidirectional"))
      (node (ref "CLAMP2") (pin "A") (pinfunction "A_A") (pintype "passive"))
      (node (ref "DRIB_TRAN") (pin "SOURCE") (pinfunction "S_SOURCE") (pintype "bidirectional"))
      (node (ref "NEON") (pin "2") (pinfunction "2_2") (pintype "passive"))
      (node (ref "Q1") (pin "E") (pinfunction "E_E") (pintype "passive"))
      (node (ref "Q2") (pin "E") (pinfunction "E_E") (pintype "passive"))
      (node (ref "R13") (pin "2") (pinfunction "2_2") (pintype "passive"))
      (node (ref "R15") (pin "1") (pinfunction "1_1") (pintype "passive"))
      (node (ref "R18") (pin "1") (pinfunction "1_1") (pintype "passive"))
      (node (ref "R21") (pin "1") (pinfunction "1_1") (pintype "passive"))
      (node (ref "R25") (pin "2") (pinfunction "2_2") (pintype "passive"))
      (node (ref "RBG") (pin "1") (pinfunction "1_1") (pintype "passive"))
      (node (ref "RSENSE") (pin "1") (pinfunction "1_1") (pintype "passive"))
      (node (ref "U$1") (pin "2") (pinfunction "GND_2") (pintype "power_in"))
      (node (ref "U$12") (pin "+") (pinfunction "+_+") (pintype "bidirectional"))
      (node (ref "U$13") (pin "2") (pinfunction "2_2") (pintype "passive"))
      (node (ref "U$16") (pin "17") (pinfunction "GNDB_17") (pintype "bidirectional"))
      (node (ref "U$16") (pin "18") (pinfunction "GNDB_18") (pintype "bidirectional"))
      (node (ref "U$16") (pin "19") (pinfunction "GNDB_19") (pintype "bidirectional"))
      (node (ref "U$16") (pin "20") (pinfunction "GNDB_20") (pintype "bidirectional"))
      (node (ref "U$16") (pin "26") (pinfunction "GNDA_26") (pintype "bidirectional"))
      (node (ref "U$16") (pin "27") (pinfunction "GNDA_27") (pintype "bidirectional"))
      (node (ref "U$16") (pin "28") (pinfunction "GNDA_28") (pintype "bidirectional"))
      (node (ref "U$16") (pin "29") (pinfunction "GNDA_29") (pintype "bidirectional"))
      (node (ref "U$19") (pin "1") (pinfunction "P$1_1") (pintype "bidirectional"))
      (node (ref "U$23") (pin "17") (pinfunction "GNDB_17") (pintype "bidirectional"))
      (node (ref "U$23") (pin "18") (pinfunction "GNDB_18") (pintype "bidirectional"))
      (node (ref "U$23") (pin "19") (pinfunction "GNDB_19") (pintype "bidirectional"))
      (node (ref "U$23") (pin "20") (pinfunction "GNDB_20") (pintype "bidirectional"))
      (node (ref "U$23") (pin "26") (pinfunction "GNDA_26") (pintype "bidirectional"))
      (node (ref "U$23") (pin "27") (pinfunction "GNDA_27") (pintype "bidirectional"))
      (node (ref "U$23") (pin "28") (pinfunction "GNDA_28") (pintype "bidirectional"))
      (node (ref "U$23") (pin "29") (pinfunction "GNDA_29") (pintype "bidirectional"))
      (node (ref "U$25") (pin "17") (pinfunction "GNDB_17") (pintype "bidirectional"))
      (node (ref "U$25") (pin "18") (pinfunction "GNDB_18") (pintype "bidirectional"))
      (node (ref "U$25") (pin "19") (pinfunction "GNDB_19") (pintype "bidirectional"))
      (node (ref "U$25") (pin "20") (pinfunction "GNDB_20") (pintype "bidirectional"))
      (node (ref "U$25") (pin "26") (pinfunction "GNDA_26") (pintype "bidirectional"))
      (node (ref "U$25") (pin "27") (pinfunction "GNDA_27") (pintype "bidirectional"))
      (node (ref "U$25") (pin "28") (pinfunction "GNDA_28") (pintype "bidirectional"))
      (node (ref "U$25") (pin "29") (pinfunction "GNDA_29") (pintype "bidirectional"))
      (node (ref "U$27") (pin "17") (pinfunction "GNDB_17") (pintype "bidirectional"))
      (node (ref "U$27") (pin "18") (pinfunction "GNDB_18") (pintype "bidirectional"))
      (node (ref "U$27") (pin "19") (pinfunction "GNDB_19") (pintype "bidirectional"))
      (node (ref "U$27") (pin "20") (pinfunction "GNDB_20") (pintype "bidirectional"))
      (node (ref "U$27") (pin "26") (pinfunction "GNDA_26") (pintype "bidirectional"))
      (node (ref "U$27") (pin "27") (pinfunction "GNDA_27") (pintype "bidirectional"))
      (node (ref "U$27") (pin "28") (pinfunction "GNDA_28") (pintype "bidirectional"))
      (node (ref "U$27") (pin "29") (pinfunction "GNDA_29") (pintype "bidirectional"))
      (node (ref "U$3") (pin "P$10") (pinfunction "P$10_P$10") (pintype "bidirectional"))
      (node (ref "U$4") (pin "2") (pinfunction "GND_2") (pintype "power_in"))
      (node (ref "U$5") (pin "3") (pinfunction "S2_3") (pintype "bidirectional"))
      (node (ref "U$6") (pin "LEFT") (pinfunction "COLLECTOR_LEFT") (pintype "bidirectional"))
    )
    (net (code "6") (name "/BAT+") (class "Default")
      (node (ref "BATT") (pin "1") (pinfunction "KL_1") (pintype "passive"))
      (node (ref "ON/OFF") (pin "COM") (pinfunction "COM_COM") (pintype "bidirectional"))
      (node (ref "ON/OFF") (pin "IN1") (pinfunction "P1_IN1") (pintype "bidirectional"))
    )
    (net (code "7") (name "/BATSENSE") (class "Default")
      (node (ref "BAT") (pin "P$1") (pinfunction "P$1_P$1") (pintype "bidirectional"))
      (node (ref "BATCLAMP2") (pin "C") (pinfunction "C_C") (pintype "passive"))
      (node (ref "R17") (pin "1") (pinfunction "1_1") (pintype "passive"))
      (node (ref "R18") (pin "2") (pinfunction "2_2") (pintype "passive"))
      (node (ref "U$14") (pin "23/A9") (pinfunction "23/A9_23/A9") (pintype "bidirectional"))
    )
    (net (code "8") (name "/BB_IN") (class "Default")
      (node (ref "BB_CON") (pin "2") (pinfunction "P$2_2") (pintype "bidirectional"))
      (node (ref "U$14") (pin "31/A12") (pinfunction "31/A12_31/A12") (pintype "bidirectional"))
    )
    (net (code "9") (name "/BB_OUT") (class "Default")
      (node (ref "R19") (pin "1") (pinfunction "1_1") (pintype "passive"))
      (node (ref "U$14") (pin "32/A13") (pinfunction "32/A13_32/A13") (pintype "bidirectional"))
    )
    (net (code "10") (name "/CAP+") (class "Default")
      (node (ref "C14") (pin "+") (pinfunction "+_+") (pintype "passive"))
      (node (ref "C6") (pin "+") (pinfunction "+_+") (pintype "passive"))
      (node (ref "CAP+_TEST") (pin "P$1") (pinfunction "P$1_P$1") (pintype "bidirectional"))
      (node (ref "CHARGE_D") (pin "C") (pinfunction "C_C") (pintype "passive"))
      (node (ref "CHIP") (pin "1") (pinfunction "P$1_1") (pintype "bidirectional"))
      (node (ref "CHIP_FLY") (pin "CATHODE") (pinfunction "C_CATHODE") (pintype "passive"))
      (node (ref "KICK") (pin "1") (pinfunction "P$1_1") (pintype "bidirectional"))
      (node (ref "KICK_FLY") (pin "CATHODE") (pinfunction "C_CATHODE") (pintype "passive"))
      (node (ref "R14") (pin "2") (pinfunction "2_2") (pintype "passive"))
      (node (ref "R24") (pin "2") (pinfunction "2_2") (pintype "passive"))
      (node (ref "U$7") (pin "+") (pinfunction "D+_+") (pintype "bidirectional"))
    )
    (net (code "11") (name "/CHARGE") (class "Default")
      (node (ref "CHARGE") (pin "P$1") (pinfunction "P$1_P$1") (pintype "bidirectional"))
      (node (ref "CHARGE_LED") (pin "A") (pinfunction "A_A") (pintype "passive"))
      (node (ref "CHARGE_U") (pin "P$3") (pinfunction "CHRG_P$3") (pintype "bidirectional"))
      (node (ref "U$14") (pin "0/RX") (pinfunction "0/RX_0/RX") (pintype "bidirectional"))
    )
    (net (code "12") (name "/CHARGE_DONE") (class "Default")
      (node (ref "CHARGE_U") (pin "P$2") (pinfunction "~{DN}_P$2") (pintype "bidirectional"))
      (node (ref "DONE") (pin "P$1") (pinfunction "P$1_P$1") (pintype "bidirectional"))
      (node (ref "R12") (pin "2") (pinfunction "2_2") (pintype "passive"))
      (node (ref "R22") (pin "2") (pinfunction "2_2") (pintype "passive"))
      (node (ref "U$14") (pin "1/TX") (pinfunction "1/TX_1/TX") (pintype "bidirectional"))
    )
    (net (code "13") (name "/CHIP") (class "Default")
      (node (ref "ANDS") (pin "P$3") (pinfunction "Y2_P$3") (pintype "bidirectional"))
      (node (ref "CHIP_LED") (pin "A") (pinfunction "A_A") (pintype "passive"))
      (node (ref "U$1") (pin "3") (pinfunction "IN+_3") (pintype "input"))
    )
    (net (code "14") (name "/CHIP_ENABLE") (class "Default")
      (node (ref "ANDS") (pin "P$6") (pinfunction "B2_P$6") (pintype "bidirectional"))
      (node (ref "CE_LED") (pin "A") (pinfunction "A_A") (pintype "passive"))
      (node (ref "U$14") (pin "5") (pinfunction "5_5") (pintype "bidirectional"))
    )
    (net (code "15") (name "/CS_0") (class "Default")
      (node (ref "C22") (pin "1") (pinfunction "1_1") (pintype "passive"))
      (node (ref "R36") (pin "1") (pinfunction "1_1") (pintype "passive"))
      (node (ref "U$14") (pin "22/A8") (pinfunction "22/A8_22/A8") (pintype "bidirectional"))
    )
    (net (code "16") (name "/CS_1") (class "Default")
      (node (ref "C28") (pin "1") (pinfunction "1_1") (pintype "passive"))
      (node (ref "R65") (pin "1") (pinfunction "1_1") (pintype "passive"))
      (node (ref "U$14") (pin "21/A7") (pinfunction "21/A7_21/A7") (pintype "bidirectional"))
    )
    (net (code "17") (name "/CS_2") (class "Default")
      (node (ref "C32") (pin "1") (pinfunction "1_1") (pintype "passive"))
      (node (ref "R76") (pin "1") (pinfunction "1_1") (pintype "passive"))
      (node (ref "U$14") (pin "37/A18") (pinfunction "37/A18_37/A18") (pintype "bidirectional"))
    )
    (net (code "18") (name "/CS_3") (class "Default")
      (node (ref "C45") (pin "1") (pinfunction "1_1") (pintype "passive"))
      (node (ref "R87") (pin "1") (pinfunction "1_1") (pintype "passive"))
      (node (ref "U$14") (pin "36/A17") (pinfunction "36/A17_36/A17") (pintype "bidirectional"))
    )
    (net (code "19") (name "/CTS") (class "Default")
      (node (ref "R30") (pin "1") (pinfunction "1_1") (pintype "passive"))
      (node (ref "U$14") (pin "24") (pinfunction "24_24") (pintype "bidirectional"))
    )
    (net (code "20") (name "/DISCHARGE") (class "Default")
      (node (ref "R26") (pin "1") (pinfunction "1_1") (pintype "passive"))
      (node (ref "U$14") (pin "4/CANRX") (pinfunction "4/CANRX_4/CANRX") (pintype "bidirectional"))
    )
    (net (code "21") (name "/DIVCAP") (class "Default")
      (node (ref "CAP/100") (pin "P$1") (pinfunction "P$1_P$1") (pintype "bidirectional"))
      (node (ref "CAP_SENSE_BUF") (pin "1") (pinfunction "OUT_1") (pintype "output"))
      (node (ref "CAP_SENSE_BUF") (pin "4") (pinfunction "-IN_4") (pintype "input"))
      (node (ref "R8") (pin "1") (pinfunction "1_1") (pintype "passive"))
    )
    (net (code "22") (name "/DRIB") (class "Default")
      (node (ref "DRIB_TEST") (pin "P$1") (pinfunction "P$1_P$1") (pintype "bidirectional"))
      (node (ref "DRIB_TRAN") (pin "GATE") (pinfunction "G_GATE") (pintype "bidirectional"))
      (node (ref "U$14") (pin "6") (pinfunction "6_6") (pintype "bidirectional"))
    )
    (net (code "23") (name "/ENA_0") (class "Default")
      (node (ref "R39") (pin "1") (pinfunction "1_1") (pintype "passive"))
      (node (ref "R42") (pin "1") (pinfunction "1_1") (pintype "passive"))
      (node (ref "U$17") (pin "2") (pinfunction "GPB1_2") (pintype "bidirectional"))
    )
    (net (code "24") (name "/ENA_1") (class "Default")
      (node (ref "R67") (pin "1") (pinfunction "1_1") (pintype "passive"))
      (node (ref "R70") (pin "1") (pinfunction "1_1") (pintype "passive"))
      (node (ref "U$17") (pin "27") (pinfunction "GPA6_27") (pintype "bidirectional"))
    )
    (net (code "25") (name "/ENA_2") (class "Default")
      (node (ref "R78") (pin "1") (pinfunction "1_1") (pintype "passive"))
      (node (ref "R81") (pin "1") (pinfunction "1_1") (pintype "passive"))
      (node (ref "U$21") (pin "27") (pinfunction "GPA6_27") (pintype "bidirectional"))
    )
    (net (code "26") (name "/ENA_3") (class "Default")
      (node (ref "R89") (pin "1") (pinfunction "1_1") (pintype "passive"))
      (node (ref "R92") (pin "1") (pinfunction "1_1") (pintype "passive"))
      (node (ref "U$21") (pin "2") (pinfunction "GPB1_2") (pintype "bidirectional"))
    )
    (net (code "27") (name "/ENB_0") (class "Default")
      (node (ref "R40") (pin "1") (pinfunction "1_1") (pintype "passive"))
      (node (ref "R41") (pin "1") (pinfunction "1_1") (pintype "passive"))
      (node (ref "U$17") (pin "3") (pinfunction "GPB2_3") (pintype "bidirectional"))
    )
    (net (code "28") (name "/ENB_1") (class "Default")
      (node (ref "R68") (pin "1") (pinfunction "1_1") (pintype "passive"))
      (node (ref "R69") (pin "1") (pinfunction "1_1") (pintype "passive"))
      (node (ref "U$17") (pin "26") (pinfunction "GPA5_26") (pintype "bidirectional"))
    )
    (net (code "29") (name "/ENB_2") (class "Default")
      (node (ref "R79") (pin "1") (pinfunction "1_1") (pintype "passive"))
      (node (ref "R80") (pin "1") (pinfunction "1_1") (pintype "passive"))
      (node (ref "U$21") (pin "26") (pinfunction "GPA5_26") (pintype "bidirectional"))
    )
    (net (code "30") (name "/ENB_3") (class "Default")
      (node (ref "R90") (pin "1") (pinfunction "1_1") (pintype "passive"))
      (node (ref "R91") (pin "1") (pinfunction "1_1") (pintype "passive"))
      (node (ref "U$21") (pin "3") (pinfunction "GPB2_3") (pintype "bidirectional"))
    )
    (net (code "31") (name "/GND") (class "Default")
      (node (ref "ANDS") (pin "P$4") (pinfunction "GND_P$4") (pintype "bidirectional"))
      (node (ref "BB_CON") (pin "3") (pinfunction "P$3_3") (pintype "bidirectional"))
      (node (ref "BB_CON") (pin "5") (pinfunction "P$5_5") (pintype "bidirectional"))
      (node (ref "C1") (pin "1") (pinfunction "1_1") (pintype "passive"))
      (node (ref "C10") (pin "1") (pinfunction "1_1") (pintype "passive"))
      (node (ref "C11") (pin "2") (pinfunction "2_2") (pintype "passive"))
      (node (ref "C12") (pin "2") (pinfunction "2_2") (pintype "passive"))
      (node (ref "C13") (pin "1") (pinfunction "1_1") (pintype "passive"))
      (node (ref "C15") (pin "2") (pinfunction "2_2") (pintype "passive"))
      (node (ref "C22") (pin "2") (pinfunction "2_2") (pintype "passive"))
      (node (ref "C28") (pin "2") (pinfunction "2_2") (pintype "passive"))
      (node (ref "C32") (pin "2") (pinfunction "2_2") (pintype "passive"))
      (node (ref "C33") (pin "2") (pinfunction "2_2") (pintype "passive"))
      (node (ref "C35") (pin "2") (pinfunction "2_2") (pintype "passive"))
      (node (ref "C36") (pin "2") (pinfunction "2_2") (pintype "passive"))
      (node (ref "C37") (pin "2") (pinfunction "2_2") (pintype "passive"))
      (node (ref "C38") (pin "2") (pinfunction "2_2") (pintype "passive"))
      (node (ref "C39") (pin "2") (pinfunction "2_2") (pintype "passive"))
      (node (ref "C45") (pin "2") (pinfunction "2_2") (pintype "passive"))
      (node (ref "C8") (pin "2") (pinfunction "2_2") (pintype "passive"))
      (node (ref "C9") (pin "2") (pinfunction "2_2") (pintype "passive"))
      (node (ref "D2") (pin "A") (pinfunction "A_A") (pintype "passive"))
      (node (ref "GND") (pin "P$1") (pinfunction "P$1_P$1") (pintype "bidirectional"))
      (node (ref "IC1") (pin "4") (pinfunction "GND_4") (pintype "power_in"))
      (node (ref "JP1") (pin "3") (pinfunction "3_3") (pintype "passive"))
      (node (ref "JP2") (pin "3") (pinfunction "3_3") (pintype "passive"))
      (node (ref "JP3") (pin "3") (pinfunction "3_3") (pintype "passive"))
      (node (ref "JP4") (pin "3") (pinfunction "3_3") (pintype "passive"))
      (node (ref "R10") (pin "1") (pinfunction "1_1") (pintype "passive"))
      (node (ref "R11") (pin "2") (pinfunction "2_2") (pintype "passive"))
      (node (ref "R4") (pin "2") (pinfunction "2_2") (pintype "passive"))
      (node (ref "R45") (pin "2") (pinfunction "2_2") (pintype "passive"))
      (node (ref "R47") (pin "2") (pinfunction "2_2") (pintype "passive"))
      (node (ref "R49") (pin "2") (pinfunction "2_2") (pintype "passive"))
      (node (ref "R5") (pin "2") (pinfunction "2_2") (pintype "passive"))
      (node (ref "R51") (pin "2") (pinfunction "2_2") (pintype "passive"))
      (node (ref "R53") (pin "2") (pinfunction "2_2") (pintype "passive"))
      (node (ref "R55") (pin "2") (pinfunction "2_2") (pintype "passive"))
      (node (ref "R57") (pin "2") (pinfunction "2_2") (pintype "passive"))
      (node (ref "R59") (pin "2") (pinfunction "2_2") (pintype "passive"))
      (node (ref "R60") (pin "1") (pinfunction "1_1") (pintype "passive"))
      (node (ref "R61") (pin "1") (pinfunction "1_1") (pintype "passive"))
      (node (ref "R71") (pin "1") (pinfunction "1_1") (pintype "passive"))
      (node (ref "R72") (pin "1") (pinfunction "1_1") (pintype "passive"))
      (node (ref "R82") (pin "1") (pinfunction "1_1") (pintype "passive"))
      (node (ref "R83") (pin "1") (pinfunction "1_1") (pintype "passive"))
      (node (ref "R9") (pin "1") (pinfunction "1_1") (pintype "passive"))
      (node (ref "R93") (pin "1") (pinfunction "1_1") (pintype "passive"))
      (node (ref "R94") (pin "1") (pinfunction "1_1") (pintype "passive"))
      (node (ref "U$14") (pin "AGND") (pinfunction "AGND_AGND") (pintype "bidirectional"))
      (node (ref "U$14") (pin "GND") (pinfunction "GND_GND") (pintype "bidirectional"))
      (node (ref "U$14") (pin "GND2") (pinfunction "GND2_GND2") (pintype "bidirectional"))
      (node (ref "U$15") (pin "10") (pinfunction "GND_10") (pintype "power_in"))
      (node (ref "U$17") (pin "10") (pinfunction "VSS_10") (pintype "bidirectional"))
      (node (ref "U$17") (pin "15") (pinfunction "A0_15") (pintype "bidirectional"))
      (node (ref "U$17") (pin "16") (pinfunction "A1_16") (pintype "bidirectional"))
      (node (ref "U$17") (pin "17") (pinfunction "A2_17") (pintype "bidirectional"))
      (node (ref "U$18") (pin "1") (pinfunction "EOUT_1") (pintype "bidirectional"))
      (node (ref "U$18") (pin "4") (pinfunction "VCC_4") (pintype "bidirectional"))
      (node (ref "U$19") (pin "2") (pinfunction "P$2_2") (pintype "bidirectional"))
      (node (ref "U$21") (pin "10") (pinfunction "VSS_10") (pintype "bidirectional"))
      (node (ref "U$21") (pin "15") (pinfunction "A0_15") (pintype "bidirectional"))
      (node (ref "U$21") (pin "16") (pinfunction "A1_16") (pintype "bidirectional"))
      (node (ref "U$22") (pin "S") (pinfunction "S_S") (pintype "bidirectional"))
      (node (ref "U$5") (pin "2") (pinfunction "LED-_2") (pintype "bidirectional"))
      (node (ref "U$8") (pin "1") (pinfunction "GND_1") (pintype "bidirectional"))
    )
    (net (code "32") (name "/INA_0") (class "Default")
      (node (ref "R63") (pin "2") (pinfunction "2_2") (pintype "passive"))
      (node (ref "U$17") (pin "1") (pinfunction "GPB0_1") (pintype "bidirectional"))
    )
    (net (code "33") (name "/INA_1") (class "Default")
      (node (ref "R74") (pin "2") (pinfunction "2_2") (pintype "passive"))
      (node (ref "U$17") (pin "28") (pinfunction "GPA7_28") (pintype "bidirectional"))
    )
    (net (code "34") (name "/INA_2") (class "Default")
      (node (ref "R85") (pin "2") (pinfunction "2_2") (pintype "passive"))
      (node (ref "U$21") (pin "28") (pinfunction "GPA7_28") (pintype "bidirectional"))
    )
    (net (code "35") (name "/INA_3") (class "Default")
      (node (ref "R96") (pin "2") (pinfunction "2_2") (pintype "passive"))
      (node (ref "U$21") (pin "1") (pinfunction "GPB0_1") (pintype "bidirectional"))
    )
    (net (code "36") (name "/INB_0") (class "Default")
      (node (ref "R62") (pin "2") (pinfunction "2_2") (pintype "passive"))
      (node (ref "U$17") (pin "4") (pinfunction "GPB3_4") (pintype "bidirectional"))
    )
    (net (code "37") (name "/INB_1") (class "Default")
      (node (ref "R73") (pin "2") (pinfunction "2_2") (pintype "passive"))
      (node (ref "U$17") (pin "25") (pinfunction "GPA4_25") (pintype "bidirectional"))
    )
    (net (code "38") (name "/INB_2") (class "Default")
      (node (ref "R84") (pin "2") (pinfunction "2_2") (pintype "passive"))
      (node (ref "U$21") (pin "25") (pinfunction "GPA4_25") (pintype "bidirectional"))
    )
    (net (code "39") (name "/INB_3") (class "Default")
      (node (ref "R95") (pin "2") (pinfunction "2_2") (pintype "passive"))
      (node (ref "U$21") (pin "4") (pinfunction "GPB3_4") (pintype "bidirectional"))
    )
    (net (code "40") (name "/INT1") (class "Default")
      (node (ref "U$14") (pin "9/CS") (pinfunction "9/CS_9/CS") (pintype "bidirectional"))
      (node (ref "U$17") (pin "20") (pinfunction "INTA_20") (pintype "bidirectional"))
    )
    (net (code "41") (name "/INT2") (class "Default")
      (node (ref "U$14") (pin "39/A20") (pinfunction "39/A20_39/A20") (pintype "bidirectional"))
      (node (ref "U$21") (pin "20") (pinfunction "INTA_20") (pintype "bidirectional"))
    )
    (net (code "42") (name "/KICK") (class "Default")
      (node (ref "ANDS") (pin "P$7") (pinfunction "Y1_P$7") (pintype "bidirectional"))
      (node (ref "KICK_LED") (pin "A") (pinfunction "A_A") (pintype "passive"))
      (node (ref "U$4") (pin "3") (pinfunction "IN+_3") (pintype "input"))
    )
    (net (code "43") (name "/KICK_ENABLE") (class "Default")
      (node (ref "ANDS") (pin "P$2") (pinfunction "B1_P$2") (pintype "bidirectional"))
      (node (ref "KE_LED") (pin "A") (pinfunction "A_A") (pintype "passive"))
      (node (ref "U$14") (pin "7") (pinfunction "7_7") (pintype "bidirectional"))
    )
    (net (code "44") (name "/KICK_REF") (class "Default")
      (node (ref "R37") (pin "1") (pinfunction "1_1") (pintype "passive"))
      (node (ref "U$14") (pin "A22/DAC1") (pinfunction "A22/DAC1_A22/DAC1") (pintype "bidirectional"))
    )
    (net (code "45") (name "/M1QA-1") (class "Default")
      (node (ref "JP1") (pin "5") (pinfunction "5_5") (pintype "passive"))
      (node (ref "R58") (pin "2") (pinfunction "2_2") (pintype "passive"))
    )
    (net (code "46") (name "/M1QA-1OUT") (class "Default")
      (node (ref "R58") (pin "1") (pinfunction "1_1") (pintype "passive"))
      (node (ref "R59") (pin "1") (pinfunction "1_1") (pintype "passive"))
      (node (ref "U$14") (pin "17/A3") (pinfunction "17/A3_17/A3") (pintype "bidirectional"))
    )
    (net (code "47") (name "/M1QA-2") (class "Default")
      (node (ref "JP2") (pin "5") (pinfunction "5_5") (pintype "passive"))
      (node (ref "R52") (pin "2") (pinfunction "2_2") (pintype "passive"))
    )
    (net (code "48") (name "/M1QA-2OUT") (class "Default")
      (node (ref "R52") (pin "1") (pinfunction "1_1") (pintype "passive"))
      (node (ref "R53") (pin "1") (pinfunction "1_1") (pintype "passive"))
      (node (ref "U$14") (pin "27") (pinfunction "27_27") (pintype "bidirectional"))
    )
    (net (code "49") (name "/M1QA-3") (class "Default")
      (node (ref "JP3") (pin "5") (pinfunction "5_5") (pintype "passive"))
      (node (ref "R54") (pin "2") (pinfunction "2_2") (pintype "passive"))
    )
    (net (code "50") (name "/M1QA-3OUT") (class "Default")
      (node (ref "R54") (pin "1") (pinfunction "1_1") (pintype "passive"))
      (node (ref "R55") (pin "1") (pinfunction "1_1") (pintype "passive"))
      (node (ref "U$14") (pin "15/A1") (pinfunction "15/A1_15/A1") (pintype "bidirectional"))
    )
    (net (code "51") (name "/M1QA-4") (class "Default")
      (node (ref "JP4") (pin "5") (pinfunction "5_5") (pintype "passive"))
      (node (ref "R56") (pin "2") (pinfunction "2_2") (pintype "passive"))
    )
    (net (code "52") (name "/M1QA-4OUT") (class "Default")
      (node (ref "R56") (pin "1") (pinfunction "1_1") (pintype "passive"))
      (node (ref "R57") (pin "1") (pinfunction "1_1") (pintype "passive"))
      (node (ref "U$14") (pin "25") (pinfunction "25_25") (pintype "bidirectional"))
    )
    (net (code "53") (name "/M1QB-1") (class "Default")
      (node (ref "JP1") (pin "6") (pinfunction "6_6") (pintype "passive"))
      (node (ref "R50") (pin "2") (pinfunction "2_2") (pintype "passive"))
    )
    (net (code "54") (name "/M1QB-1OUT") (class "Default")
      (node (ref "R50") (pin "1") (pinfunction "1_1") (pintype "passive"))
      (node (ref "R51") (pin "1") (pinfunction "1_1") (pintype "passive"))
      (node (ref "U$14") (pin "16/A2") (pinfunction "16/A2_16/A2") (pintype "bidirectional"))
    )
    (net (code "55") (name "/M1QB-2") (class "Default")
      (node (ref "JP2") (pin "6") (pinfunction "6_6") (pintype "passive"))
      (node (ref "R44") (pin "2") (pinfunction "2_2") (pintype "passive"))
    )
    (net (code "56") (name "/M1QB-2OUT") (class "Default")
      (node (ref "R44") (pin "1") (pinfunction "1_1") (pintype "passive"))
      (node (ref "R45") (pin "1") (pinfunction "1_1") (pintype "passive"))
      (node (ref "U$14") (pin "28") (pinfunction "28_28") (pintype "bidirectional"))
    )
    (net (code "57") (name "/M1QB-3") (class "Default")
      (node (ref "JP3") (pin "6") (pinfunction "6_6") (pintype "passive"))
      (node (ref "R46") (pin "2") (pinfunction "2_2") (pintype "passive"))
    )
    (net (code "58") (name "/M1QB-3OUT") (class "Default")
      (node (ref "R46") (pin "1") (pinfunction "1_1") (pintype "passive"))
      (node (ref "R47") (pin "1") (pinfunction "1_1") (pintype "passive"))
      (node (ref "U$14") (pin "14/A0") (pinfunction "14/A0_14/A0") (pintype "bidirectional"))
    )
    (net (code "59") (name "/M1QB-4") (class "Default")
      (node (ref "JP4") (pin "6") (pinfunction "6_6") (pintype "passive"))
      (node (ref "R48") (pin "2") (pinfunction "2_2") (pintype "passive"))
    )
    (net (code "60") (name "/M1QB-4OUT") (class "Default")
      (node (ref "R48") (pin "1") (pinfunction "1_1") (pintype "passive"))
      (node (ref "R49") (pin "1") (pinfunction "1_1") (pintype "passive"))
      (node (ref "U$14") (pin "26") (pinfunction "26_26") (pintype "bidirectional"))
    )
    (net (code "61") (name "/N$38") (class "Default")
      (node (ref "C13") (pin "2") (pinfunction "2_2") (pintype "passive"))
      (node (ref "R32") (pin "1") (pinfunction "1_1") (pintype "passive"))
      (node (ref "U$8") (pin "7") (pinfunction "VREF2_7") (pintype "bidirectional"))
      (node (ref "U$8") (pin "8") (pinfunction "EN_8") (pintype "bidirectional"))
    )
    (net (code "62") (name "/OUTA_0") (class "Default")
      (node (ref "GREEN_DIR") (pin "C") (pinfunction "C_C") (pintype "passive"))
      (node (ref "JP1") (pin "1") (pinfunction "1_1") (pintype "passive"))
      (node (ref "RED_DIR") (pin "A") (pinfunction "A_A") (pintype "passive"))
      (node (ref "U$16") (pin "1") (pinfunction "OUTA_1") (pintype "bidirectional"))
      (node (ref "U$16") (pin "24") (pinfunction "OUTA_24") (pintype "bidirectional"))
      (node (ref "U$16") (pin "25") (pinfunction "OUTA_25") (pintype "bidirectional"))
      (node (ref "U$16") (pin "30") (pinfunction "OUTA_30") (pintype "bidirectional"))
      (node (ref "U$16") (pin "OUTA") (pinfunction "OUTA_OUTA") (pintype "bidirectional"))
      (node (ref "U$16") (pin "OUTA@1") (pinfunction "OUTA_OUTA@1") (pintype "bidirectional"))
    )
    (net (code "63") (name "/OUTA_1") (class "Default")
      (node (ref "GREEN_DIR1") (pin "C") (pinfunction "C_C") (pintype "passive"))
      (node (ref "JP2") (pin "1") (pinfunction "1_1") (pintype "passive"))
      (node (ref "RED_DIR1") (pin "A") (pinfunction "A_A") (pintype "passive"))
      (node (ref "U$23") (pin "1") (pinfunction "OUTA_1") (pintype "bidirectional"))
      (node (ref "U$23") (pin "24") (pinfunction "OUTA_24") (pintype "bidirectional"))
      (node (ref "U$23") (pin "25") (pinfunction "OUTA_25") (pintype "bidirectional"))
      (node (ref "U$23") (pin "30") (pinfunction "OUTA_30") (pintype "bidirectional"))
      (node (ref "U$23") (pin "OUTA") (pinfunction "OUTA_OUTA") (pintype "bidirectional"))
      (node (ref "U$23") (pin "OUTA@1") (pinfunction "OUTA_OUTA@1") (pintype "bidirectional"))
    )
    (net (code "64") (name "/OUTA_2") (class "Default")
      (node (ref "GREEN_DIR2") (pin "C") (pinfunction "C_C") (pintype "passive"))
      (node (ref "JP3") (pin "1") (pinfunction "1_1") (pintype "passive"))
      (node (ref "RED_DIR2") (pin "A") (pinfunction "A_A") (pintype "passive"))
      (node (ref "U$25") (pin "1") (pinfunction "OUTA_1") (pintype "bidirectional"))
      (node (ref "U$25") (pin "24") (pinfunction "OUTA_24") (pintype "bidirectional"))
      (node (ref "U$25") (pin "25") (pinfunction "OUTA_25") (pintype "bidirectional"))
      (node (ref "U$25") (pin "30") (pinfunction "OUTA_30") (pintype "bidirectional"))
      (node (ref "U$25") (pin "OUTA") (pinfunction "OUTA_OUTA") (pintype "bidirectional"))
      (node (ref "U$25") (pin "OUTA@1") (pinfunction "OUTA_OUTA@1") (pintype "bidirectional"))
    )
    (net (code "65") (name "/OUTA_3") (class "Default")
      (node (ref "GREEN_DIR3") (pin "C") (pinfunction "C_C") (pintype "passive"))
      (node (ref "JP4") (pin "1") (pinfunction "1_1") (pintype "passive"))
      (node (ref "RED_DIR3") (pin "A") (pinfunction "A_A") (pintype "passive"))
      (node (ref "U$27") (pin "1") (pinfunction "OUTA_1") (pintype "bidirectional"))
      (node (ref "U$27") (pin "24") (pinfunction "OUTA_24") (pintype "bidirectional"))
      (node (ref "U$27") (pin "25") (pinfunction "OUTA_25") (pintype "bidirectional"))
      (node (ref "U$27") (pin "30") (pinfunction "OUTA_30") (pintype "bidirectional"))
      (node (ref "U$27") (pin "OUTA") (pinfunction "OUTA_OUTA") (pintype "bidirectional"))
      (node (ref "U$27") (pin "OUTA@1") (pinfunction "OUTA_OUTA@1") (pintype "bidirectional"))
    )
    (net (code "66") (name "/OUTB_0") (class "Default")
      (node (ref "JP1") (pin "2") (pinfunction "2_2") (pintype "passive"))
      (node (ref "R38") (pin "1") (pinfunction "1_1") (pintype "passive"))
      (node (ref "U$16") (pin "15") (pinfunction "OUTB_15") (pintype "bidirectional"))
      (node (ref "U$16") (pin "16") (pinfunction "OUTB_16") (pintype "bidirectional"))
      (node (ref "U$16") (pin "21") (pinfunction "OUTB_21") (pintype "bidirectional"))
      (node (ref "U$16") (pin "22") (pinfunction "OUTB_22") (pintype "bidirectional"))
      (node (ref "U$16") (pin "OUTB") (pinfunction "OUTB_OUTB") (pintype "bidirectional"))
      (node (ref "U$16") (pin "OUTB@1") (pinfunction "OUTB_OUTB@1") (pintype "bidirectional"))
    )
    (net (code "67") (name "/OUTB_1") (class "Default")
      (node (ref "JP2") (pin "2") (pinfunction "2_2") (pintype "passive"))
      (node (ref "R66") (pin "1") (pinfunction "1_1") (pintype "passive"))
      (node (ref "U$23") (pin "15") (pinfunction "OUTB_15") (pintype "bidirectional"))
      (node (ref "U$23") (pin "16") (pinfunction "OUTB_16") (pintype "bidirectional"))
      (node (ref "U$23") (pin "21") (pinfunction "OUTB_21") (pintype "bidirectional"))
      (node (ref "U$23") (pin "22") (pinfunction "OUTB_22") (pintype "bidirectional"))
      (node (ref "U$23") (pin "OUTB") (pinfunction "OUTB_OUTB") (pintype "bidirectional"))
      (node (ref "U$23") (pin "OUTB@1") (pinfunction "OUTB_OUTB@1") (pintype "bidirectional"))
    )
    (net (code "68") (name "/OUTB_2") (class "Default")
      (node (ref "JP3") (pin "2") (pinfunction "2_2") (pintype "passive"))
      (node (ref "R77") (pin "1") (pinfunction "1_1") (pintype "passive"))
      (node (ref "U$25") (pin "15") (pinfunction "OUTB_15") (pintype "bidirectional"))
      (node (ref "U$25") (pin "16") (pinfunction "OUTB_16") (pintype "bidirectional"))
      (node (ref "U$25") (pin "21") (pinfunction "OUTB_21") (pintype "bidirectional"))
      (node (ref "U$25") (pin "22") (pinfunction "OUTB_22") (pintype "bidirectional"))
      (node (ref "U$25") (pin "OUTB") (pinfunction "OUTB_OUTB") (pintype "bidirectional"))
      (node (ref "U$25") (pin "OUTB@1") (pinfunction "OUTB_OUTB@1") (pintype "bidirectional"))
    )
    (net (code "69") (name "/OUTB_3") (class "Default")
      (node (ref "JP4") (pin "2") (pinfunction "2_2") (pintype "passive"))
      (node (ref "R88") (pin "1") (pinfunction "1_1") (pintype "passive"))
      (node (ref "U$27") (pin "15") (pinfunction "OUTB_15") (pintype "bidirectional"))
      (node (ref "U$27") (pin "16") (pinfunction "OUTB_16") (pintype "bidirectional"))
      (node (ref "U$27") (pin "21") (pinfunction "OUTB_21") (pintype "bidirectional"))
      (node (ref "U$27") (pin "22") (pinfunction "OUTB_22") (pintype "bidirectional"))
      (node (ref "U$27") (pin "OUTB") (pinfunction "OUTB_OUTB") (pintype "bidirectional"))
      (node (ref "U$27") (pin "OUTB@1") (pinfunction "OUTB_OUTB@1") (pintype "bidirectional"))
    )
    (net (code "70") (name "/PWM0") (class "Default")
      (node (ref "R35") (pin "1") (pinfunction "1_1") (pintype "passive"))
      (node (ref "R60") (pin "2") (pinfunction "2_2") (pintype "passive"))
      (node (ref "U$14") (pin "2") (pinfunction "2_2") (pintype "bidirectional"))
    )
    (net (code "71") (name "/PWM1") (class "Default")
      (node (ref "R64") (pin "1") (pinfunction "1_1") (pintype "passive"))
      (node (ref "R71") (pin "2") (pinfunction "2_2") (pintype "passive"))
      (node (ref "U$14") (pin "3/CANTX") (pinfunction "3/CANTX_3/CANTX") (pintype "bidirectional"))
    )
    (net (code "72") (name "/PWM2") (class "Default")
      (node (ref "R75") (pin "1") (pinfunction "1_1") (pintype "passive"))
      (node (ref "R82") (pin "2") (pinfunction "2_2") (pintype "passive"))
      (node (ref "U$14") (pin "10/CS") (pinfunction "10/CS_10/CS") (pintype "bidirectional"))
    )
    (net (code "73") (name "/PWM3") (class "Default")
      (node (ref "R86") (pin "1") (pinfunction "1_1") (pintype "passive"))
      (node (ref "R93") (pin "2") (pinfunction "2_2") (pintype "passive"))
      (node (ref "U$14") (pin "29") (pinfunction "29_29") (pintype "bidirectional"))
    )
    (net (code "74") (name "/RTS") (class "Default")
      (node (ref "R28") (pin "1") (pinfunction "1_1") (pintype "passive"))
      (node (ref "U$14") (pin "35/A16") (pinfunction "35/A16_35/A16") (pintype "bidirectional"))
    )
    (net (code "75") (name "/RX") (class "Default")
      (node (ref "U$14") (pin "34/A15") (pinfunction "34/A15_34/A15") (pintype "bidirectional"))
      (node (ref "U$15") (pin "2") (pinfunction "DOUT_2") (pintype "output"))
    )
    (net (code "76") (name "/SCL") (class "Default")
      (node (ref "R27") (pin "1") (pinfunction "1_1") (pintype "passive"))
      (node (ref "U$14") (pin "19/A5/SCL") (pinfunction "19/A5/SCL_19/A5/SCL") (pintype "bidirectional"))
      (node (ref "U$8") (pin "3") (pinfunction "SCL1_3") (pintype "bidirectional"))
    )
    (net (code "77") (name "/SCL-H") (class "Default")
      (node (ref "R33") (pin "1") (pinfunction "1_1") (pintype "passive"))
      (node (ref "U$17") (pin "12") (pinfunction "SCK_12") (pintype "bidirectional"))
      (node (ref "U$21") (pin "12") (pinfunction "SCK_12") (pintype "bidirectional"))
      (node (ref "U$8") (pin "6") (pinfunction "SCL2_6") (pintype "bidirectional"))
    )
    (net (code "78") (name "/SDA") (class "Default")
      (node (ref "R7") (pin "1") (pinfunction "1_1") (pintype "passive"))
      (node (ref "U$14") (pin "18/A4/SDA") (pinfunction "18/A4/SDA_18/A4/SDA") (pintype "bidirectional"))
      (node (ref "U$8") (pin "4") (pinfunction "SDA1_4") (pintype "bidirectional"))
    )
    (net (code "79") (name "/SDA-H") (class "Default")
      (node (ref "R34") (pin "1") (pinfunction "1_1") (pintype "passive"))
      (node (ref "U$17") (pin "13") (pinfunction "SDA_13") (pintype "bidirectional"))
      (node (ref "U$21") (pin "13") (pinfunction "SDA_13") (pintype "bidirectional"))
      (node (ref "U$8") (pin "5") (pinfunction "SDA2_5") (pintype "bidirectional"))
    )
    (net (code "80") (name "/SWITCHING_REG") (class "Default")
      (node (ref "IC1") (pin "7") (pinfunction "ON_7") (pintype "passive"))
    )
    (net (code "81") (name "/SWITCH_REG") (class "Default")
      (node (ref "U$14") (pin "8") (pinfunction "8_8") (pintype "bidirectional"))
    )
    (net (code "82") (name "/TX") (class "Default")
      (node (ref "U$14") (pin "33/A14") (pinfunction "33/A14_33/A14") (pintype "bidirectional"))
      (node (ref "U$15") (pin "3") (pinfunction "DIN_3") (pintype "input"))
    )
    (net (code "83") (name "/XBRST") (class "Default")
      (node (ref "U$15") (pin "5") (pinfunction "RESET_5") (pintype "input"))
    )
    (net (code "84") (name "Net-(ANDS-A1)") (class "Default")
      (node (ref "ANDS") (pin "P$1") (pinfunction "A1_P$1") (pintype "bidirectional"))
      (node (ref "ANDS") (pin "P$5") (pinfunction "A2_P$5") (pintype "bidirectional"))
      (node (ref "R29") (pin "2") (pinfunction "2_2") (pintype "passive"))
      (node (ref "U$18") (pin "7") (pinfunction "COUT_7") (pintype "bidirectional"))
      (node (ref "U$22") (pin "G") (pinfunction "G_G") (pintype "bidirectional"))
    )
    (net (code "85") (name "Net-(BB_CON-P$1)") (class "Default")
      (node (ref "BB_CON") (pin "1") (pinfunction "P$1_1") (pintype "bidirectional"))
      (node (ref "R20") (pin "2") (pinfunction "2_2") (pintype "passive"))
    )
    (net (code "86") (name "Net-(BB_CON-P$4)") (class "Default")
      (node (ref "BB_CON") (pin "4") (pinfunction "P$4_4") (pintype "bidirectional"))
      (node (ref "R19") (pin "2") (pinfunction "2_2") (pintype "passive"))
    )
    (net (code "87") (name "Net-(CAP_SENSE_BUF-+IN)") (class "Default")
      (node (ref "CAP_SENSE_BUF") (pin "3") (pinfunction "+IN_3") (pintype "input"))
      (node (ref "CLAMP1") (pin "A") (pinfunction "A_A") (pintype "passive"))
      (node (ref "CLAMP2") (pin "C") (pinfunction "C_C") (pintype "passive"))
      (node (ref "R14") (pin "1") (pinfunction "1_1") (pintype "passive"))
      (node (ref "R15") (pin "2") (pinfunction "2_2") (pintype "passive"))
    )
    (net (code "88") (name "Net-(CE_LED-PadC)") (class "Default")
      (node (ref "CE_LED") (pin "C") (pinfunction "C_C") (pintype "passive"))
      (node (ref "R5") (pin "1") (pinfunction "1_1") (pintype "passive"))
    )
    (net (code "89") (name "Net-(CHARGE_D-PadA)") (class "Default")
      (node (ref "CHARGE_D") (pin "A") (pinfunction "A_A") (pintype "passive"))
      (node (ref "U$3") (pin "P$1") (pinfunction "P$1_P$1") (pintype "bidirectional"))
    )
    (net (code "90") (name "Net-(CHARGE_LED-PadC)") (class "Default")
      (node (ref "CHARGE_LED") (pin "C") (pinfunction "C_C") (pintype "passive"))
      (node (ref "R11") (pin "1") (pinfunction "1_1") (pintype "passive"))
    )
    (net (code "91") (name "Net-(CHARGE_U-GATE)") (class "Default")
      (node (ref "CHARGE_U") (pin "P$7") (pinfunction "GATE_P$7") (pintype "bidirectional"))
      (node (ref "R43") (pin "1") (pinfunction "1_1") (pintype "passive"))
    )
    (net (code "92") (name "Net-(CHARGE_U-RBG)") (class "Default")
      (node (ref "C19") (pin "1") (pinfunction "1_1") (pintype "passive"))
      (node (ref "CHARGE_U") (pin "P$10") (pinfunction "RBG_P$10") (pintype "bidirectional"))
      (node (ref "RBG") (pin "2") (pinfunction "2_2") (pintype "passive"))
    )
    (net (code "93") (name "Net-(CHARGE_U-RDCM)") (class "Default")
      (node (ref "CHARGE_U") (pin "P$8") (pinfunction "RDCM_P$8") (pintype "bidirectional"))
      (node (ref "R31") (pin "1") (pinfunction "1_1") (pintype "passive"))
    )
    (net (code "94") (name "Net-(CHARGE_U-RV)") (class "Default")
      (node (ref "CHARGE_U") (pin "P$9") (pinfunction "RV_P$9") (pintype "bidirectional"))
      (node (ref "RVOUT") (pin "1") (pinfunction "1_1") (pintype "passive"))
    )
    (net (code "95") (name "Net-(CHARGE_U-SRC)") (class "Default")
      (node (ref "CHARGE_U") (pin "P$6") (pinfunction "SRC_P$6") (pintype "bidirectional"))
      (node (ref "RSENSE") (pin "2") (pinfunction "2_2") (pintype "passive"))
      (node (ref "SWITCH_Q") (pin "SOURCE") (pinfunction "S_SOURCE") (pintype "bidirectional"))
    )
    (net (code "96") (name "Net-(CHIP-P$2)") (class "Default")
      (node (ref "CHIP") (pin "2") (pinfunction "P$2_2") (pintype "bidirectional"))
      (node (ref "CHIP_FLY") (pin "ANODE") (pinfunction "A_ANODE") (pintype "passive"))
      (node (ref "Q2") (pin "C@1") (pinfunction "C_C@1") (pintype "passive"))
      (node (ref "Q2") (pin "C@2") (pinfunction "C_C@2") (pintype "passive"))
    )
    (net (code "97") (name "Net-(CHIP_LED-PadC)") (class "Default")
      (node (ref "CHIP_LED") (pin "C") (pinfunction "C_C") (pintype "passive"))
      (node (ref "R10") (pin "2") (pinfunction "2_2") (pintype "passive"))
    )
    (net (code "98") (name "Net-(DONE_LED-PadC)") (class "Default")
      (node (ref "DONE_LED") (pin "C") (pinfunction "C_C") (pintype "passive"))
      (node (ref "R12") (pin "1") (pinfunction "1_1") (pintype "passive"))
    )
    (net (code "99") (name "Net-(DRIB-P$2)") (class "Default")
      (node (ref "DRIB") (pin "2") (pinfunction "P$2_2") (pintype "bidirectional"))
      (node (ref "DRIB_TRAN") (pin "DRAIN") (pinfunction "D_DRAIN") (pintype "bidirectional"))
    )
    (net (code "100") (name "Net-(GREEN_DIR-PadA)") (class "Default")
      (node (ref "GREEN_DIR") (pin "A") (pinfunction "A_A") (pintype "passive"))
      (node (ref "R38") (pin "2") (pinfunction "2_2") (pintype "passive"))
      (node (ref "RED_DIR") (pin "C") (pinfunction "C_C") (pintype "passive"))
    )
    (net (code "101") (name "Net-(GREEN_DIR1-PadA)") (class "Default")
      (node (ref "GREEN_DIR1") (pin "A") (pinfunction "A_A") (pintype "passive"))
      (node (ref "R66") (pin "2") (pinfunction "2_2") (pintype "passive"))
      (node (ref "RED_DIR1") (pin "C") (pinfunction "C_C") (pintype "passive"))
    )
    (net (code "102") (name "Net-(GREEN_DIR2-PadA)") (class "Default")
      (node (ref "GREEN_DIR2") (pin "A") (pinfunction "A_A") (pintype "passive"))
      (node (ref "R77") (pin "2") (pinfunction "2_2") (pintype "passive"))
      (node (ref "RED_DIR2") (pin "C") (pinfunction "C_C") (pintype "passive"))
    )
    (net (code "103") (name "Net-(GREEN_DIR3-PadA)") (class "Default")
      (node (ref "GREEN_DIR3") (pin "A") (pinfunction "A_A") (pintype "passive"))
      (node (ref "R88") (pin "2") (pinfunction "2_2") (pintype "passive"))
      (node (ref "RED_DIR3") (pin "C") (pinfunction "C_C") (pintype "passive"))
    )
    (net (code "104") (name "Net-(IC1-CB)") (class "Default")
      (node (ref "C46") (pin "1") (pinfunction "1_1") (pintype "passive"))
      (node (ref "IC1") (pin "3") (pinfunction "CB_3") (pintype "input"))
    )
    (net (code "105") (name "Net-(IC1-FB)") (class "Default")
      (node (ref "3.3V1") (pin "P$1") (pinfunction "P$1_P$1") (pintype "bidirectional"))
      (node (ref "C11") (pin "1") (pinfunction "1_1") (pintype "passive"))
      (node (ref "C39") (pin "1") (pinfunction "1_1") (pintype "passive"))
      (node (ref "IC1") (pin "6") (pinfunction "FB_6") (pintype "input"))
      (node (ref "U$9") (pin "P$2") (pinfunction "P$2_P$2") (pintype "bidirectional"))
    )
    (net (code "106") (name "Net-(IC1-VSW)") (class "Default")
      (node (ref "C46") (pin "2") (pinfunction "2_2") (pintype "passive"))
      (node (ref "D2") (pin "C") (pinfunction "C_C") (pintype "passive"))
      (node (ref "IC1") (pin "1") (pinfunction "VSW_1") (pintype "output"))
      (node (ref "U$9") (pin "P$1") (pinfunction "P$1_P$1") (pintype "bidirectional"))
    )
    (net (code "107") (name "Net-(KE_LED-PadC)") (class "Default")
      (node (ref "KE_LED") (pin "C") (pinfunction "C_C") (pintype "passive"))
      (node (ref "R4") (pin "1") (pinfunction "1_1") (pintype "passive"))
    )
    (net (code "108") (name "Net-(KICK-P$2)") (class "Default")
      (node (ref "KICK") (pin "2") (pinfunction "P$2_2") (pintype "bidirectional"))
      (node (ref "KICK_FLY") (pin "ANODE") (pinfunction "A_ANODE") (pintype "passive"))
      (node (ref "Q1") (pin "C@1") (pinfunction "C_C@1") (pintype "passive"))
      (node (ref "Q1") (pin "C@2") (pinfunction "C_C@2") (pintype "passive"))
    )
    (net (code "109") (name "Net-(KICK_LED-PadC)") (class "Default")
      (node (ref "KICK_LED") (pin "C") (pinfunction "C_C") (pintype "passive"))
      (node (ref "R9") (pin "2") (pinfunction "2_2") (pintype "passive"))
    )
    (net (code "110") (name "Net-(KICK_READY-PadC)") (class "Default")
      (node (ref "KICK_READY") (pin "C") (pinfunction "C_C") (pintype "passive"))
      (node (ref "R6") (pin "2") (pinfunction "2_2") (pintype "passive"))
    )
    (net (code "111") (name "Net-(NEON-Pad1)") (class "Default")
      (node (ref "NEON") (pin "1") (pinfunction "1_1") (pintype "passive"))
      (node (ref "R24") (pin "1") (pinfunction "1_1") (pintype "passive"))
    )
    (net (code "112") (name "Net-(PW_LED1-PadC)") (class "Default")
      (node (ref "PW_LED1") (pin "C") (pinfunction "C_C") (pintype "passive"))
      (node (ref "R21") (pin "2") (pinfunction "2_2") (pintype "passive"))
    )
    (net (code "113") (name "Net-(Q1-PadG)") (class "Default")
      (node (ref "Q1") (pin "G") (pinfunction "G_G") (pintype "passive"))
      (node (ref "R1") (pin "2") (pinfunction "2_2") (pintype "passive"))
    )
    (net (code "114") (name "Net-(Q2-PadG)") (class "Default")
      (node (ref "Q2") (pin "G") (pinfunction "G_G") (pintype "passive"))
      (node (ref "R2") (pin "2") (pinfunction "2_2") (pintype "passive"))
    )
    (net (code "115") (name "Net-(R6-Pad1)") (class "Default")
      (node (ref "R6") (pin "1") (pinfunction "1_1") (pintype "passive"))
      (node (ref "U$22") (pin "D") (pinfunction "D_D") (pintype "bidirectional"))
    )
    (net (code "116") (name "Net-(SWITCH_Q-D)") (class "Default")
      (node (ref "DRAIN") (pin "P$1") (pinfunction "P$1_P$1") (pintype "bidirectional"))
      (node (ref "R31") (pin "2") (pinfunction "2_2") (pintype "passive"))
      (node (ref "RVOUT") (pin "2") (pinfunction "2_2") (pintype "passive"))
      (node (ref "SWITCH_Q") (pin "DRAIN") (pinfunction "D_DRAIN") (pintype "bidirectional"))
      (node (ref "U$3") (pin "P$6") (pinfunction "P$6_P$6") (pintype "bidirectional"))
      (node (ref "U$3") (pin "P$7") (pinfunction "P$7_P$7") (pintype "bidirectional"))
    )
    (net (code "117") (name "Net-(SWITCH_Q-G)") (class "Default")
      (node (ref "GATE") (pin "P$1") (pinfunction "P$1_P$1") (pintype "bidirectional"))
      (node (ref "R43") (pin "2") (pinfunction "2_2") (pintype "passive"))
      (node (ref "SWITCH_Q") (pin "GATE") (pinfunction "G_GATE") (pintype "bidirectional"))
    )
    (net (code "118") (name "Net-(U$1-OUT)") (class "Default")
      (node (ref "R2") (pin "1") (pinfunction "1_1") (pintype "passive"))
      (node (ref "U$1") (pin "5") (pinfunction "OUT_5") (pintype "output"))
    )
    (net (code "119") (name "Net-(U$2-DRAIN)") (class "Default")
      (node (ref "U$2") (pin "TAB") (pinfunction "DRAIN_TAB") (pintype "bidirectional"))
      (node (ref "U$7") (pin "-") (pinfunction "D-_-") (pintype "bidirectional"))
    )
    (net (code "120") (name "Net-(U$2-GATE)") (class "Default")
      (node (ref "R25") (pin "1") (pinfunction "1_1") (pintype "passive"))
      (node (ref "U$2") (pin "LOWER_LEFT") (pinfunction "GATE_LOWER_LEFT") (pintype "bidirectional"))
    )
    (net (code "121") (name "Net-(U$2-SOURCE)") (class "Default")
      (node (ref "R3") (pin "1") (pinfunction "1_1") (pintype "passive"))
      (node (ref "U$2") (pin "LOWER_RIGHT") (pinfunction "SOURCE_LOWER_RIGHT") (pintype "bidirectional"))
      (node (ref "U$6") (pin "RIGHT") (pinfunction "EMITTER_RIGHT") (pintype "bidirectional"))
    )
    (net (code "122") (name "Net-(U$4-OUT)") (class "Default")
      (node (ref "R1") (pin "1") (pinfunction "1_1") (pintype "passive"))
      (node (ref "U$4") (pin "5") (pinfunction "OUT_5") (pintype "output"))
    )
    (net (code "123") (name "Net-(U$5-LED+)") (class "Default")
      (node (ref "R26") (pin "2") (pinfunction "2_2") (pintype "passive"))
      (node (ref "U$5") (pin "1") (pinfunction "LED+_1") (pintype "bidirectional"))
    )
    (net (code "124") (name "Net-(U$5-S1)") (class "Default")
      (node (ref "R16") (pin "1") (pinfunction "1_1") (pintype "passive"))
      (node (ref "R23") (pin "2") (pinfunction "2_2") (pintype "passive"))
      (node (ref "U$5") (pin "4") (pinfunction "S1_4") (pintype "bidirectional"))
    )
    (net (code "125") (name "Net-(U$6-BASE)") (class "Default")
      (node (ref "R13") (pin "1") (pinfunction "1_1") (pintype "passive"))
      (node (ref "R16") (pin "2") (pinfunction "2_2") (pintype "passive"))
      (node (ref "R3") (pin "2") (pinfunction "2_2") (pintype "passive"))
      (node (ref "U$6") (pin "CENTER") (pinfunction "BASE_CENTER") (pintype "bidirectional"))
    )
    (net (code "126") (name "Net-(U$15-CTS)") (class "Default")
      (node (ref "R30") (pin "2") (pinfunction "2_2") (pintype "passive"))
      (node (ref "U$15") (pin "12") (pinfunction "CTS_12") (pintype "output"))
    )
    (net (code "127") (name "Net-(U$15-RTS)") (class "Default")
      (node (ref "R28") (pin "2") (pinfunction "2_2") (pintype "passive"))
      (node (ref "U$15") (pin "16") (pinfunction "RTS_16") (pintype "input"))
    )
    (net (code "128") (name "Net-(U$16-CP)") (class "Default")
      (node (ref "U$16") (pin "11") (pinfunction "CP_11") (pintype "bidirectional"))
      (node (ref "U$20") (pin "1") (pinfunction "G_1") (pintype "bidirectional"))
    )
    (net (code "129") (name "Net-(U$16-CS)") (class "Default")
      (node (ref "R36") (pin "2") (pinfunction "2_2") (pintype "passive"))
      (node (ref "R61") (pin "2") (pinfunction "2_2") (pintype "passive"))
      (node (ref "U$16") (pin "8") (pinfunction "CS_8") (pintype "bidirectional"))
    )
    (net (code "130") (name "Net-(U$16-ENA{slash}DIAGA)") (class "Default")
      (node (ref "R39") (pin "2") (pinfunction "2_2") (pintype "passive"))
      (node (ref "U$16") (pin "5") (pinfunction "ENA/DIAGA_5") (pintype "bidirectional"))
    )
    (net (code "131") (name "Net-(U$16-ENB{slash}DIAGB)") (class "Default")
      (node (ref "R40") (pin "2") (pinfunction "2_2") (pintype "passive"))
      (node (ref "U$16") (pin "9") (pinfunction "ENB/DIAGB_9") (pintype "bidirectional"))
    )
    (net (code "132") (name "Net-(U$16-INA)") (class "Default")
      (node (ref "R63") (pin "1") (pinfunction "1_1") (pintype "passive"))
      (node (ref "U$16") (pin "4") (pinfunction "INA_4") (pintype "bidirectional"))
    )
    (net (code "133") (name "Net-(U$16-INB)") (class "Default")
      (node (ref "R62") (pin "1") (pinfunction "1_1") (pintype "passive"))
      (node (ref "U$16") (pin "10") (pinfunction "INB_10") (pintype "bidirectional"))
    )
    (net (code "134") (name "Net-(U$16-PWM)") (class "Default")
      (node (ref "R35") (pin "2") (pinfunction "2_2") (pintype "passive"))
      (node (ref "U$16") (pin "7") (pinfunction "PWM_7") (pintype "bidirectional"))
    )
    (net (code "135") (name "Net-(U$18-IN+)") (class "Default")
      (node (ref "R8") (pin "2") (pinfunction "2_2") (pintype "passive"))
      (node (ref "U$18") (pin "2") (pinfunction "IN+_2") (pintype "bidirectional"))
    )
    (net (code "136") (name "Net-(U$18-IN-)") (class "Default")
      (node (ref "R37") (pin "2") (pinfunction "2_2") (pintype "passive"))
      (node (ref "U$18") (pin "3") (pinfunction "IN-_3") (pintype "bidirectional"))
    )
    (net (code "137") (name "Net-(U$20-S)") (class "Default")
      (node (ref "C17") (pin "1") (pinfunction "1_1") (pintype "passive"))
      (node (ref "C24") (pin "1") (pinfunction "1_1") (pintype "passive"))
      (node (ref "U$16") (pin "13") (pinfunction "VCC_13") (pintype "bidirectional"))
      (node (ref "U$16") (pin "14") (pinfunction "VCC_14") (pintype "bidirectional"))
      (node (ref "U$16") (pin "2") (pinfunction "VCC_2") (pintype "bidirectional"))
      (node (ref "U$16") (pin "23") (pinfunction "VCC_23") (pintype "bidirectional"))
      (node (ref "U$16") (pin "3") (pinfunction "VCC_3") (pintype "bidirectional"))
      (node (ref "U$16") (pin "VCC") (pinfunction "VCC_VCC") (pintype "bidirectional"))
      (node (ref "U$16") (pin "VCC@1") (pinfunction "VCC_VCC@1") (pintype "bidirectional"))
      (node (ref "U$20") (pin "3") (pinfunction "S_3") (pintype "bidirectional"))
    )
    (net (code "138") (name "Net-(U$23-CP)") (class "Default")
      (node (ref "U$23") (pin "11") (pinfunction "CP_11") (pintype "bidirectional"))
      (node (ref "U$24") (pin "1") (pinfunction "G_1") (pintype "bidirectional"))
    )
    (net (code "139") (name "Net-(U$23-CS)") (class "Default")
      (node (ref "R65") (pin "2") (pinfunction "2_2") (pintype "passive"))
      (node (ref "R72") (pin "2") (pinfunction "2_2") (pintype "passive"))
      (node (ref "U$23") (pin "8") (pinfunction "CS_8") (pintype "bidirectional"))
    )
    (net (code "140") (name "Net-(U$23-ENA{slash}DIAGA)") (class "Default")
      (node (ref "R67") (pin "2") (pinfunction "2_2") (pintype "passive"))
      (node (ref "U$23") (pin "5") (pinfunction "ENA/DIAGA_5") (pintype "bidirectional"))
    )
    (net (code "141") (name "Net-(U$23-ENB{slash}DIAGB)") (class "Default")
      (node (ref "R68") (pin "2") (pinfunction "2_2") (pintype "passive"))
      (node (ref "U$23") (pin "9") (pinfunction "ENB/DIAGB_9") (pintype "bidirectional"))
    )
    (net (code "142") (name "Net-(U$23-INA)") (class "Default")
      (node (ref "R74") (pin "1") (pinfunction "1_1") (pintype "passive"))
      (node (ref "U$23") (pin "4") (pinfunction "INA_4") (pintype "bidirectional"))
    )
    (net (code "143") (name "Net-(U$23-INB)") (class "Default")
      (node (ref "R73") (pin "1") (pinfunction "1_1") (pintype "passive"))
      (node (ref "U$23") (pin "10") (pinfunction "INB_10") (pintype "bidirectional"))
    )
    (net (code "144") (name "Net-(U$23-PWM)") (class "Default")
      (node (ref "R64") (pin "2") (pinfunction "2_2") (pintype "passive"))
      (node (ref "U$23") (pin "7") (pinfunction "PWM_7") (pintype "bidirectional"))
    )
    (net (code "145") (name "Net-(U$24-S)") (class "Default")
      (node (ref "C26") (pin "1") (pinfunction "1_1") (pintype "passive"))
      (node (ref "C27") (pin "1") (pinfunction "1_1") (pintype "passive"))
      (node (ref "U$23") (pin "13") (pinfunction "VCC_13") (pintype "bidirectional"))
      (node (ref "U$23") (pin "14") (pinfunction "VCC_14") (pintype "bidirectional"))
      (node (ref "U$23") (pin "2") (pinfunction "VCC_2") (pintype "bidirectional"))
      (node (ref "U$23") (pin "23") (pinfunction "VCC_23") (pintype "bidirectional"))
      (node (ref "U$23") (pin "3") (pinfunction "VCC_3") (pintype "bidirectional"))
      (node (ref "U$23") (pin "VCC") (pinfunction "VCC_VCC") (pintype "bidirectional"))
      (node (ref "U$23") (pin "VCC@1") (pinfunction "VCC_VCC@1") (pintype "bidirectional"))
      (node (ref "U$24") (pin "3") (pinfunction "S_3") (pintype "bidirectional"))
    )
    (net (code "146") (name "Net-(U$25-CP)") (class "Default")
      (node (ref "U$25") (pin "11") (pinfunction "CP_11") (pintype "bidirectional"))
      (node (ref "U$26") (pin "1") (pinfunction "G_1") (pintype "bidirectional"))
    )
    (net (code "147") (name "Net-(U$25-CS)") (class "Default")
      (node (ref "R76") (pin "2") (pinfunction "2_2") (pintype "passive"))
      (node (ref "R83") (pin "2") (pinfunction "2_2") (pintype "passive"))
      (node (ref "U$25") (pin "8") (pinfunction "CS_8") (pintype "bidirectional"))
    )
    (net (code "148") (name "Net-(U$25-ENA{slash}DIAGA)") (class "Default")
      (node (ref "R78") (pin "2") (pinfunction "2_2") (pintype "passive"))
      (node (ref "U$25") (pin "5") (pinfunction "ENA/DIAGA_5") (pintype "bidirectional"))
    )
    (net (code "149") (name "Net-(U$25-ENB{slash}DIAGB)") (class "Default")
      (node (ref "R79") (pin "2") (pinfunction "2_2") (pintype "passive"))
      (node (ref "U$25") (pin "9") (pinfunction "ENB/DIAGB_9") (pintype "bidirectional"))
    )
    (net (code "150") (name "Net-(U$25-INA)") (class "Default")
      (node (ref "R85") (pin "1") (pinfunction "1_1") (pintype "passive"))
      (node (ref "U$25") (pin "4") (pinfunction "INA_4") (pintype "bidirectional"))
    )
    (net (code "151") (name "Net-(U$25-INB)") (class "Default")
      (node (ref "R84") (pin "1") (pinfunction "1_1") (pintype "passive"))
      (node (ref "U$25") (pin "10") (pinfunction "INB_10") (pintype "bidirectional"))
    )
    (net (code "152") (name "Net-(U$25-PWM)") (class "Default")
      (node (ref "R75") (pin "2") (pinfunction "2_2") (pintype "passive"))
      (node (ref "U$25") (pin "7") (pinfunction "PWM_7") (pintype "bidirectional"))
    )
    (net (code "153") (name "Net-(U$26-S)") (class "Default")
      (node (ref "C30") (pin "1") (pinfunction "1_1") (pintype "passive"))
      (node (ref "C31") (pin "1") (pinfunction "1_1") (pintype "passive"))
      (node (ref "U$25") (pin "13") (pinfunction "VCC_13") (pintype "bidirectional"))
      (node (ref "U$25") (pin "14") (pinfunction "VCC_14") (pintype "bidirectional"))
      (node (ref "U$25") (pin "2") (pinfunction "VCC_2") (pintype "bidirectional"))
      (node (ref "U$25") (pin "23") (pinfunction "VCC_23") (pintype "bidirectional"))
      (node (ref "U$25") (pin "3") (pinfunction "VCC_3") (pintype "bidirectional"))
      (node (ref "U$25") (pin "VCC") (pinfunction "VCC_VCC") (pintype "bidirectional"))
      (node (ref "U$25") (pin "VCC@1") (pinfunction "VCC_VCC@1") (pintype "bidirectional"))
      (node (ref "U$26") (pin "3") (pinfunction "S_3") (pintype "bidirectional"))
    )
    (net (code "154") (name "Net-(U$27-CP)") (class "Default")
      (node (ref "U$27") (pin "11") (pinfunction "CP_11") (pintype "bidirectional"))
      (node (ref "U$28") (pin "1") (pinfunction "G_1") (pintype "bidirectional"))
    )
    (net (code "155") (name "Net-(U$27-CS)") (class "Default")
      (node (ref "R87") (pin "2") (pinfunction "2_2") (pintype "passive"))
      (node (ref "R94") (pin "2") (pinfunction "2_2") (pintype "passive"))
      (node (ref "U$27") (pin "8") (pinfunction "CS_8") (pintype "bidirectional"))
    )
    (net (code "156") (name "Net-(U$27-ENA{slash}DIAGA)") (class "Default")
      (node (ref "R89") (pin "2") (pinfunction "2_2") (pintype "passive"))
      (node (ref "U$27") (pin "5") (pinfunction "ENA/DIAGA_5") (pintype "bidirectional"))
    )
    (net (code "157") (name "Net-(U$27-ENB{slash}DIAGB)") (class "Default")
      (node (ref "R90") (pin "2") (pinfunction "2_2") (pintype "passive"))
      (node (ref "U$27") (pin "9") (pinfunction "ENB/DIAGB_9") (pintype "bidirectional"))
    )
    (net (code "158") (name "Net-(U$27-INA)") (class "Default")
      (node (ref "R96") (pin "1") (pinfunction "1_1") (pintype "passive"))
      (node (ref "U$27") (pin "4") (pinfunction "INA_4") (pintype "bidirectional"))
    )
    (net (code "159") (name "Net-(U$27-INB)") (class "Default")
      (node (ref "R95") (pin "1") (pinfunction "1_1") (pintype "passive"))
      (node (ref "U$27") (pin "10") (pinfunction "INB_10") (pintype "bidirectional"))
    )
    (net (code "160") (name "Net-(U$27-PWM)") (class "Default")
      (node (ref "R86") (pin "2") (pinfunction "2_2") (pintype "passive"))
      (node (ref "U$27") (pin "7") (pinfunction "PWM_7") (pintype "bidirectional"))
    )
    (net (code "161") (name "Net-(U$28-S)") (class "Default")
      (node (ref "C43") (pin "1") (pinfunction "1_1") (pintype "passive"))
      (node (ref "C44") (pin "1") (pinfunction "1_1") (pintype "passive"))
      (node (ref "U$27") (pin "13") (pinfunction "VCC_13") (pintype "bidirectional"))
      (node (ref "U$27") (pin "14") (pinfunction "VCC_14") (pintype "bidirectional"))
      (node (ref "U$27") (pin "2") (pinfunction "VCC_2") (pintype "bidirectional"))
      (node (ref "U$27") (pin "23") (pinfunction "VCC_23") (pintype "bidirectional"))
      (node (ref "U$27") (pin "3") (pinfunction "VCC_3") (pintype "bidirectional"))
      (node (ref "U$27") (pin "VCC") (pinfunction "VCC_VCC") (pintype "bidirectional"))
      (node (ref "U$27") (pin "VCC@1") (pinfunction "VCC_VCC@1") (pintype "bidirectional"))
      (node (ref "U$28") (pin "3") (pinfunction "S_3") (pintype "bidirectional"))
    )
    (net (code "162") (name "unconnected-(U$14-A21{slash}DAC0-Pad21{slash}DAC0)") (class "Default")
      (node (ref "U$14") (pin "21/DAC0") (pinfunction "A21/DAC0_21/DAC0") (pintype "bidirectional"))
    )
    (net (code "163") (name "unconnected-(U$14-Pad3V3)") (class "Default")
      (node (ref "U$14") (pin "3V3") (pinfunction "3V3_3V3") (pintype "bidirectional"))
    )
    (net (code "164") (name "unconnected-(U$14-Pad3V3_2)") (class "Default")
      (node (ref "U$14") (pin "3V3_2") (pinfunction "3V3_2_3V3_2") (pintype "bidirectional"))
    )
    (net (code "165") (name "unconnected-(U$14-Pad3V3_LO)") (class "Default")
      (node (ref "U$14") (pin "3V3_LO") (pinfunction "3V3_LO_3V3_LO") (pintype "bidirectional"))
    )
    (net (code "166") (name "unconnected-(U$14-Pad11{slash}MOSI)") (class "Default")
      (node (ref "U$14") (pin "11/MOSI") (pinfunction "11/MOSI_11/MOSI") (pintype "bidirectional"))
    )
    (net (code "167") (name "unconnected-(U$14-Pad12{slash}MISO)") (class "Default")
      (node (ref "U$14") (pin "12/MISO") (pinfunction "12/MISO_12/MISO") (pintype "bidirectional"))
    )
    (net (code "168") (name "unconnected-(U$14-Pad13{slash}SCK)") (class "Default")
      (node (ref "U$14") (pin "13/SCK") (pinfunction "13/SCK_13/SCK") (pintype "bidirectional"))
    )
    (net (code "169") (name "unconnected-(U$14-Pad20{slash}A6)") (class "Default")
      (node (ref "U$14") (pin "20/A6") (pinfunction "20/A6_20/A6") (pintype "bidirectional"))
    )
    (net (code "170") (name "unconnected-(U$14-Pad30)") (class "Default")
      (node (ref "U$14") (pin "30") (pinfunction "30_30") (pintype "bidirectional"))
    )
    (net (code "171") (name "unconnected-(U$14-Pad38{slash}A19)") (class "Default")
      (node (ref "U$14") (pin "38/A19") (pinfunction "38/A19_38/A19") (pintype "bidirectional"))
    )
    (net (code "172") (name "unconnected-(U$14-PadA10)") (class "Default")
      (node (ref "U$14") (pin "A10") (pinfunction "A10_A10") (pintype "bidirectional"))
    )
    (net (code "173") (name "unconnected-(U$14-PadA11)") (class "Default")
      (node (ref "U$14") (pin "A11") (pinfunction "A11_A11") (pintype "bidirectional"))
    )
    (net (code "174") (name "unconnected-(U$14-PadAREF)") (class "Default")
      (node (ref "U$14") (pin "AREF") (pinfunction "AREF_AREF") (pintype "bidirectional"))
    )
    (net (code "175") (name "unconnected-(U$14-PadGND3)") (class "Default")
      (node (ref "U$14") (pin "GND3") (pinfunction "GND3_GND3") (pintype "bidirectional"))
    )
    (net (code "176") (name "unconnected-(U$14-PadPROG)") (class "Default")
      (node (ref "U$14") (pin "PROG") (pinfunction "PROG_PROG") (pintype "bidirectional"))
    )
    (net (code "177") (name "unconnected-(U$14-PadRESET)") (class "Default")
      (node (ref "U$14") (pin "RESET") (pinfunction "RESET_RESET") (pintype "bidirectional"))
    )
    (net (code "178") (name "unconnected-(U$14-PadU5V)") (class "Default")
      (node (ref "U$14") (pin "U5V") (pinfunction "U5V_U5V") (pintype "bidirectional"))
    )
    (net (code "179") (name "unconnected-(U$14-PadUD+)") (class "Default")
      (node (ref "U$14") (pin "UD+") (pinfunction "UD+_UD+") (pintype "bidirectional"))
    )
    (net (code "180") (name "unconnected-(U$14-PadUD-)") (class "Default")
      (node (ref "U$14") (pin "UD-") (pinfunction "UD-_UD-") (pintype "bidirectional"))
    )
    (net (code "181") (name "unconnected-(U$14-PadUGND1)") (class "Default")
      (node (ref "U$14") (pin "UGND1") (pinfunction "UGND1_UGND1") (pintype "bidirectional"))
    )
    (net (code "182") (name "unconnected-(U$14-PadUGND2)") (class "Default")
      (node (ref "U$14") (pin "UGND2") (pinfunction "UGND2_UGND2") (pintype "bidirectional"))
    )
    (net (code "183") (name "unconnected-(U$14-PadVBAT)") (class "Default")
      (node (ref "U$14") (pin "VBAT") (pinfunction "VBAT_VBAT") (pintype "bidirectional"))
    )
    (net (code "184") (name "unconnected-(U$14-PadVUSB)") (class "Default")
      (node (ref "U$14") (pin "VUSB") (pinfunction "VUSB_VUSB") (pintype "bidirectional"))
    )
    (net (code "185") (name "unconnected-(U$15-DIO0-Pad20)") (class "Default")
      (node (ref "U$15") (pin "20") (pinfunction "DIO0_20") (pintype "bidirectional"))
    )
    (net (code "186") (name "unconnected-(U$15-DIO1-Pad19)") (class "Default")
      (node (ref "U$15") (pin "19") (pinfunction "DIO1_19") (pintype "bidirectional"))
    )
    (net (code "187") (name "unconnected-(U$15-DIO2-Pad18)") (class "Default")
      (node (ref "U$15") (pin "18") (pinfunction "DIO2_18") (pintype "bidirectional"))
    )
    (net (code "188") (name "unconnected-(U$15-DIO3-Pad17)") (class "Default")
      (node (ref "U$15") (pin "17") (pinfunction "DIO3_17") (pintype "bidirectional"))
    )
    (net (code "189") (name "unconnected-(U$15-DIO4-Pad11)") (class "Default")
      (node (ref "U$15") (pin "11") (pinfunction "DIO4_11") (pintype "bidirectional"))
    )
    (net (code "190") (name "unconnected-(U$15-DIO5-Pad15)") (class "Default")
      (node (ref "U$15") (pin "15") (pinfunction "DIO5_15") (pintype "bidirectional"))
    )
    (net (code "191") (name "unconnected-(U$15-DIO9-Pad13)") (class "Default")
      (node (ref "U$15") (pin "13") (pinfunction "DIO9_13") (pintype "bidirectional"))
    )
    (net (code "192") (name "unconnected-(U$15-DIO11-Pad7)") (class "Default")
      (node (ref "U$15") (pin "7") (pinfunction "DIO11_7") (pintype "bidirectional"))
    )
    (net (code "193") (name "unconnected-(U$15-DIO12-Pad4)") (class "Default")
      (node (ref "U$15") (pin "4") (pinfunction "DIO12_4") (pintype "bidirectional"))
    )
    (net (code "194") (name "unconnected-(U$15-DTR-Pad9)") (class "Default")
      (node (ref "U$15") (pin "9") (pinfunction "DTR_9") (pintype "bidirectional"))
    )
    (net (code "195") (name "unconnected-(U$15-RES-Pad8)") (class "Default")
      (node (ref "U$15") (pin "8") (pinfunction "RES_8") (pintype "bidirectional"))
    )
    (net (code "196") (name "unconnected-(U$15-RES-Pad14)") (class "Default")
      (node (ref "U$15") (pin "14") (pinfunction "RES_14") (pintype "bidirectional"))
    )
    (net (code "197") (name "unconnected-(U$15-RSSI-Pad6)") (class "Default")
      (node (ref "U$15") (pin "6") (pinfunction "RSSI_6") (pintype "bidirectional"))
    )
    (net (code "198") (name "unconnected-(U$16-CS_DIS-Pad6)") (class "Default")
      (node (ref "U$16") (pin "6") (pinfunction "CS_DIS_6") (pintype "bidirectional"))
    )
    (net (code "199") (name "unconnected-(U$17-GPA0-Pad21)") (class "Default")
      (node (ref "U$17") (pin "21") (pinfunction "GPA0_21") (pintype "bidirectional"))
    )
    (net (code "200") (name "unconnected-(U$17-GPA1-Pad22)") (class "Default")
      (node (ref "U$17") (pin "22") (pinfunction "GPA1_22") (pintype "bidirectional"))
    )
    (net (code "201") (name "unconnected-(U$17-GPA2-Pad23)") (class "Default")
      (node (ref "U$17") (pin "23") (pinfunction "GPA2_23") (pintype "bidirectional"))
    )
    (net (code "202") (name "unconnected-(U$17-GPA3-Pad24)") (class "Default")
      (node (ref "U$17") (pin "24") (pinfunction "GPA3_24") (pintype "bidirectional"))
    )
    (net (code "203") (name "unconnected-(U$17-GPB4-Pad5)") (class "Default")
      (node (ref "U$17") (pin "5") (pinfunction "GPB4_5") (pintype "bidirectional"))
    )
    (net (code "204") (name "unconnected-(U$17-GPB5-Pad6)") (class "Default")
      (node (ref "U$17") (pin "6") (pinfunction "GPB5_6") (pintype "bidirectional"))
    )
    (net (code "205") (name "unconnected-(U$17-GPB6-Pad7)") (class "Default")
      (node (ref "U$17") (pin "7") (pinfunction "GPB6_7") (pintype "bidirectional"))
    )
    (net (code "206") (name "unconnected-(U$17-GPB7-Pad8)") (class "Default")
      (node (ref "U$17") (pin "8") (pinfunction "GPB7_8") (pintype "bidirectional"))
    )
    (net (code "207") (name "unconnected-(U$17-INTB-Pad19)") (class "Default")
      (node (ref "U$17") (pin "19") (pinfunction "INTB_19") (pintype "bidirectional"))
    )
    (net (code "208") (name "unconnected-(U$17-NC0-Pad11)") (class "Default")
      (node (ref "U$17") (pin "11") (pinfunction "NC0_11") (pintype "bidirectional"))
    )
    (net (code "209") (name "unconnected-(U$17-NC1-Pad14)") (class "Default")
      (node (ref "U$17") (pin "14") (pinfunction "NC1_14") (pintype "bidirectional"))
    )
    (net (code "210") (name "unconnected-(U$18-BAL-Pad5)") (class "Default")
      (node (ref "U$18") (pin "5") (pinfunction "BAL_5") (pintype "bidirectional"))
    )
    (net (code "211") (name "unconnected-(U$18-BAL{slash}STRB-Pad6)") (class "Default")
      (node (ref "U$18") (pin "6") (pinfunction "BAL/STRB_6") (pintype "bidirectional"))
    )
    (net (code "212") (name "unconnected-(U$21-GPA0-Pad21)") (class "Default")
      (node (ref "U$21") (pin "21") (pinfunction "GPA0_21") (pintype "bidirectional"))
    )
    (net (code "213") (name "unconnected-(U$21-GPA1-Pad22)") (class "Default")
      (node (ref "U$21") (pin "22") (pinfunction "GPA1_22") (pintype "bidirectional"))
    )
    (net (code "214") (name "unconnected-(U$21-GPA2-Pad23)") (class "Default")
      (node (ref "U$21") (pin "23") (pinfunction "GPA2_23") (pintype "bidirectional"))
    )
    (net (code "215") (name "unconnected-(U$21-GPA3-Pad24)") (class "Default")
      (node (ref "U$21") (pin "24") (pinfunction "GPA3_24") (pintype "bidirectional"))
    )
    (net (code "216") (name "unconnected-(U$21-GPB4-Pad5)") (class "Default")
      (node (ref "U$21") (pin "5") (pinfunction "GPB4_5") (pintype "bidirectional"))
    )
    (net (code "217") (name "unconnected-(U$21-GPB5-Pad6)") (class "Default")
      (node (ref "U$21") (pin "6") (pinfunction "GPB5_6") (pintype "bidirectional"))
    )
    (net (code "218") (name "unconnected-(U$21-GPB6-Pad7)") (class "Default")
      (node (ref "U$21") (pin "7") (pinfunction "GPB6_7") (pintype "bidirectional"))
    )
    (net (code "219") (name "unconnected-(U$21-GPB7-Pad8)") (class "Default")
      (node (ref "U$21") (pin "8") (pinfunction "GPB7_8") (pintype "bidirectional"))
    )
    (net (code "220") (name "unconnected-(U$21-INTB-Pad19)") (class "Default")
      (node (ref "U$21") (pin "19") (pinfunction "INTB_19") (pintype "bidirectional"))
    )
    (net (code "221") (name "unconnected-(U$21-NC0-Pad11)") (class "Default")
      (node (ref "U$21") (pin "11") (pinfunction "NC0_11") (pintype "bidirectional"))
    )
    (net (code "222") (name "unconnected-(U$21-NC1-Pad14)") (class "Default")
      (node (ref "U$21") (pin "14") (pinfunction "NC1_14") (pintype "bidirectional"))
    )
    (net (code "223") (name "unconnected-(U$23-CS_DIS-Pad6)") (class "Default")
      (node (ref "U$23") (pin "6") (pinfunction "CS_DIS_6") (pintype "bidirectional"))
    )
    (net (code "224") (name "unconnected-(U$25-CS_DIS-Pad6)") (class "Default")
      (node (ref "U$25") (pin "6") (pinfunction "CS_DIS_6") (pintype "bidirectional"))
    )
    (net (code "225") (name "unconnected-(U$27-CS_DIS-Pad6)") (class "Default")
      (node (ref "U$27") (pin "6") (pinfunction "CS_DIS_6") (pintype "bidirectional"))
    )
  )
)
